# thermo_final.net
KiCad netlist of a schematic drawn in EAGLE
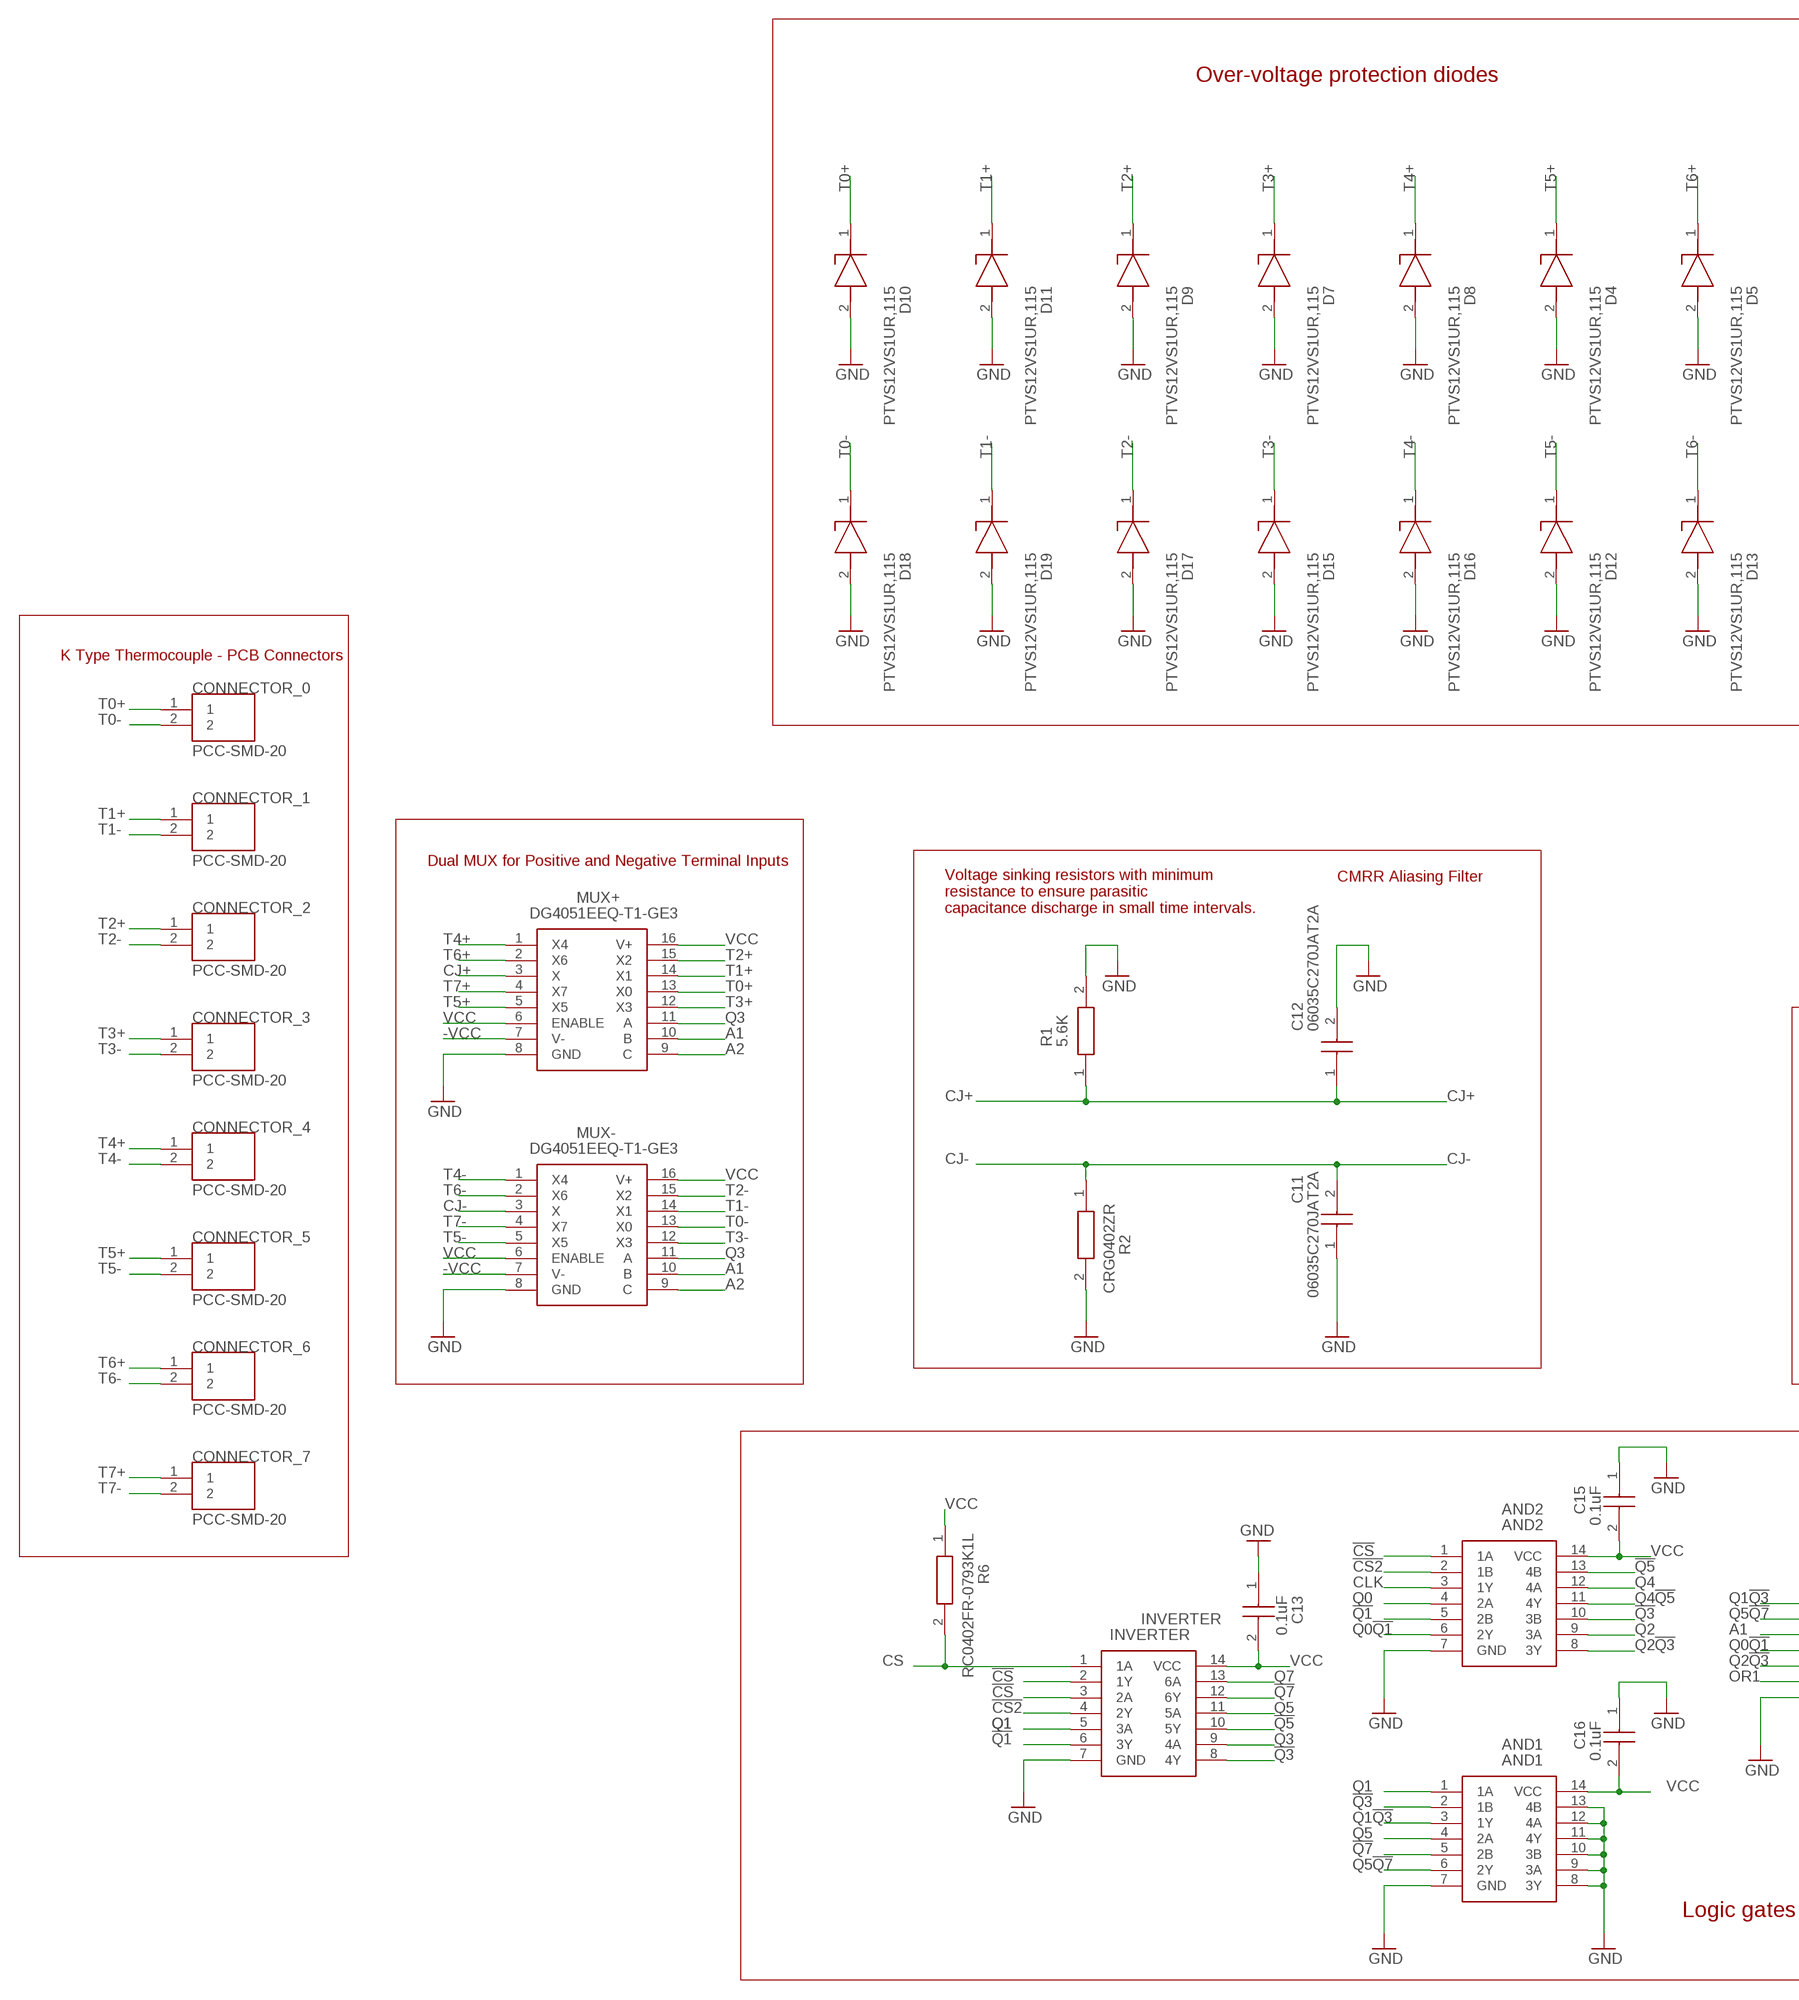
[diagram p0: schematic, sheet 1, part 1 of 2]
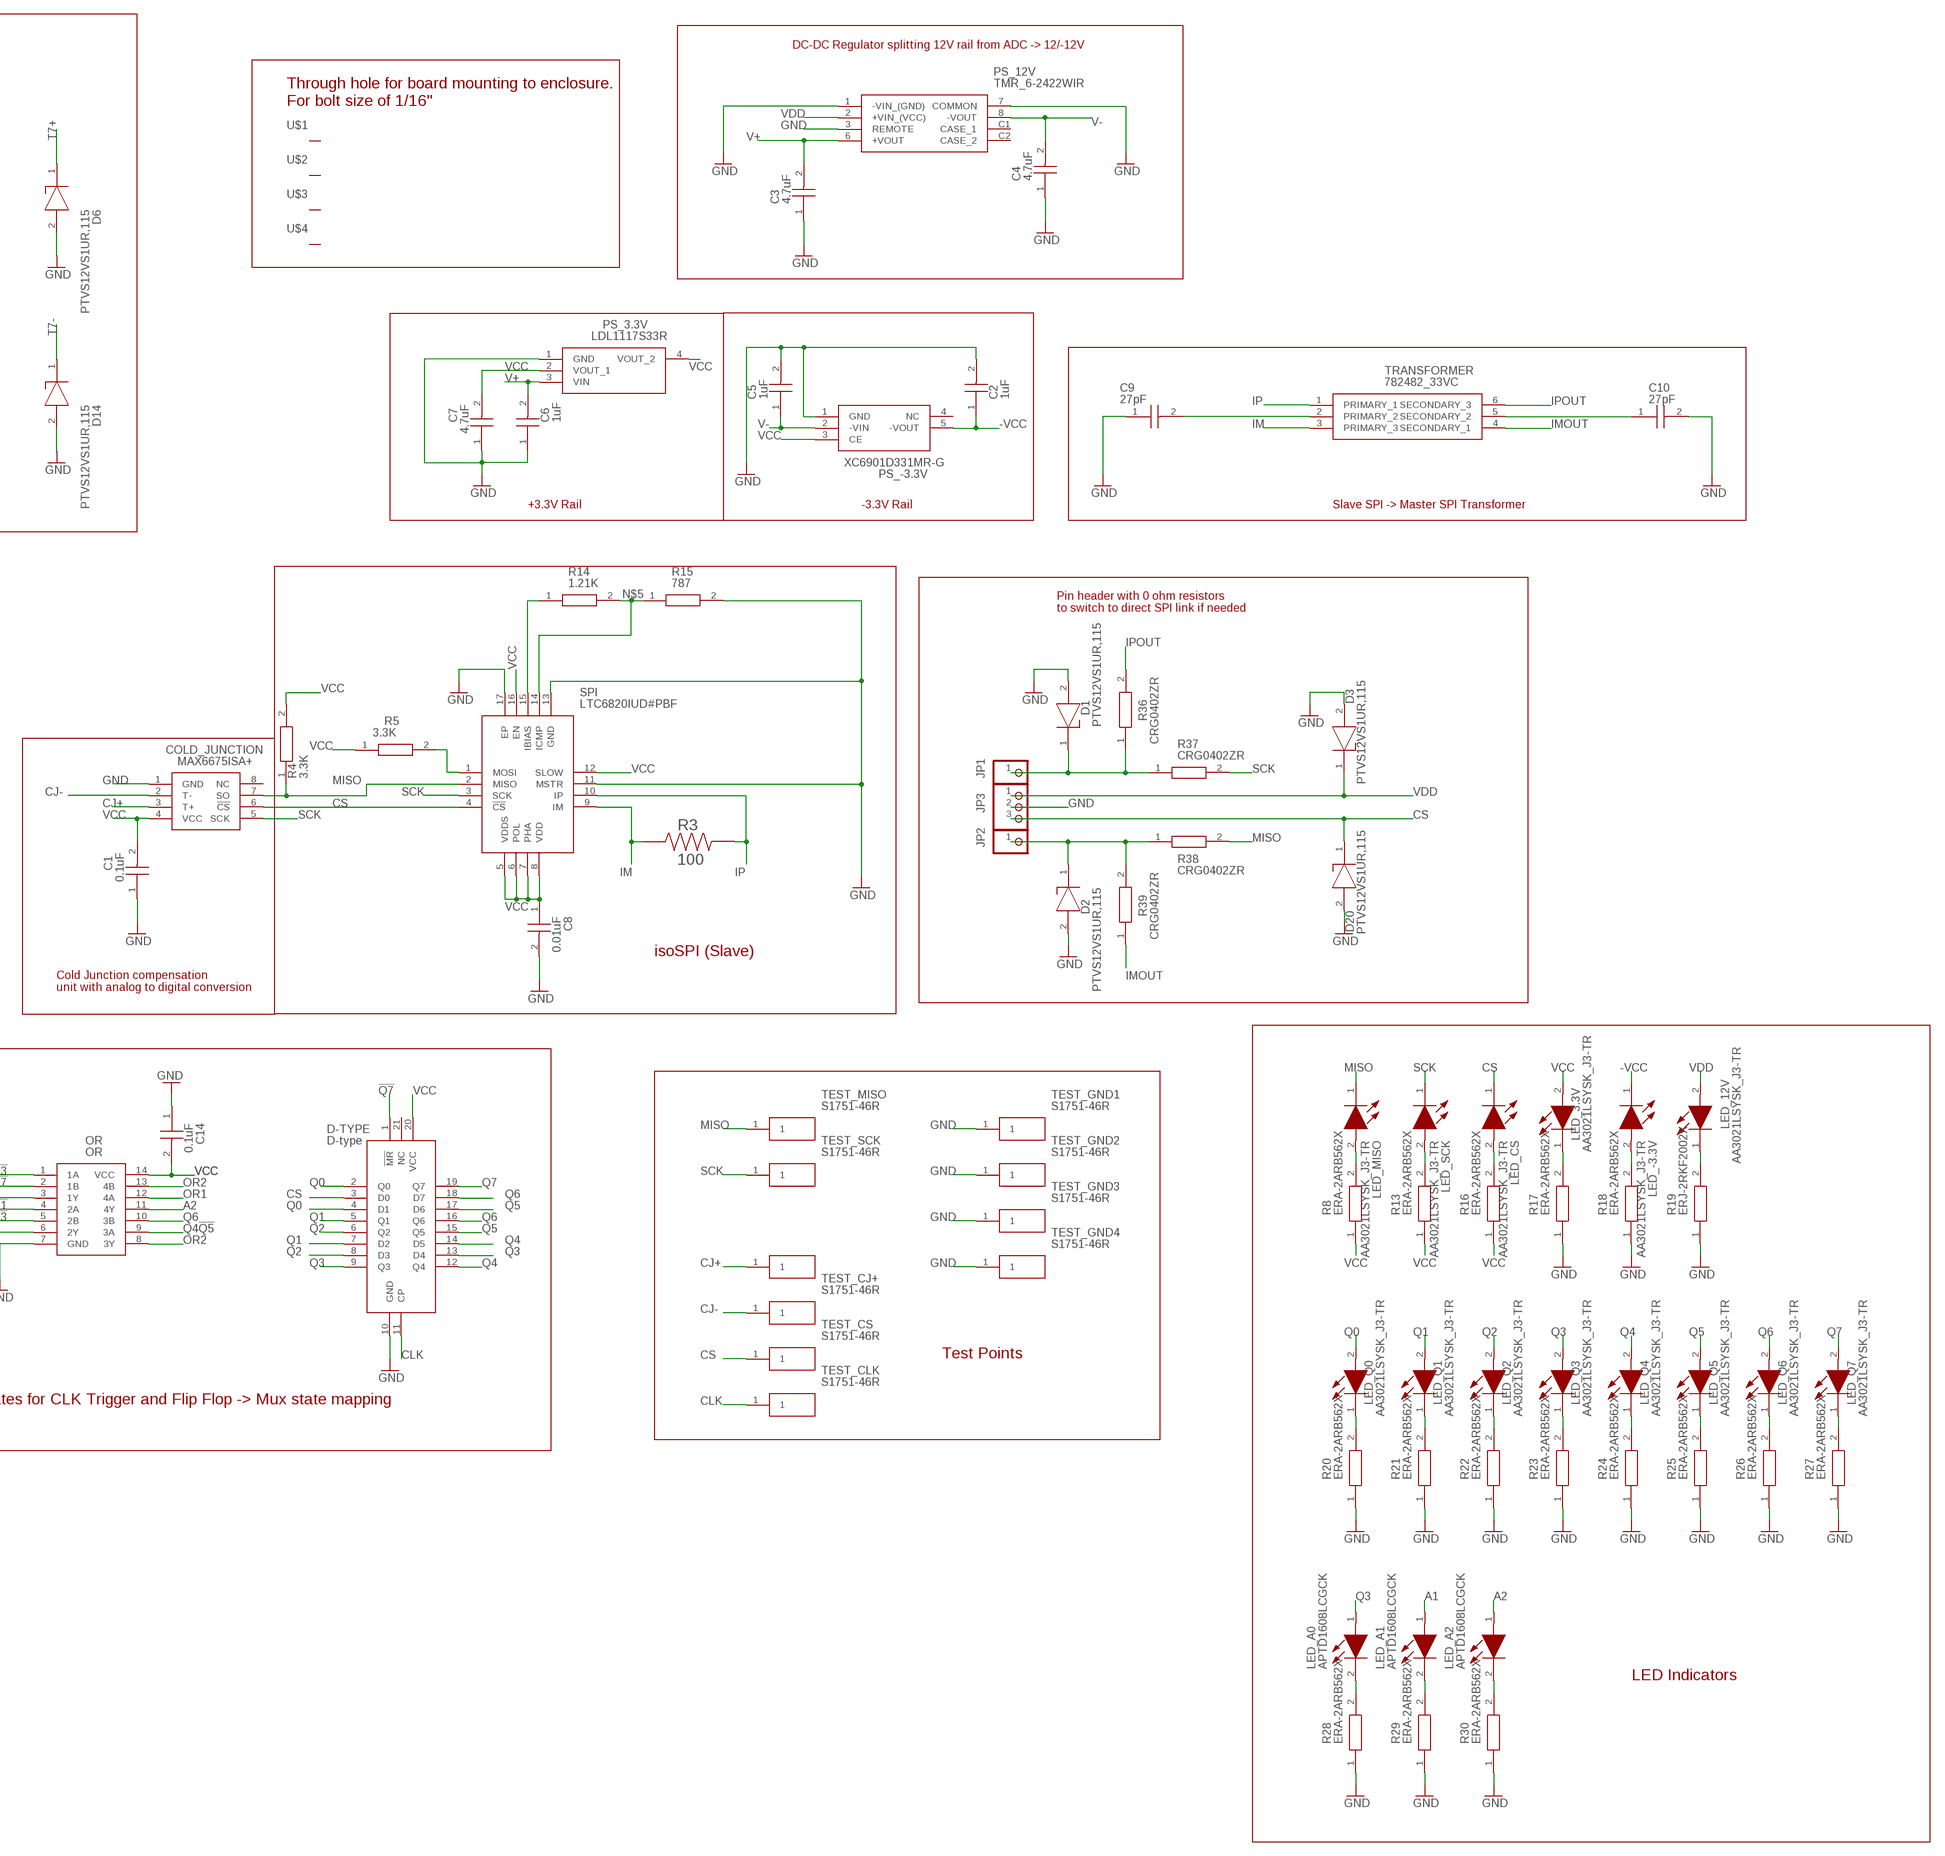
[diagram p1: schematic, sheet 1, part 2 of 2]

(export (version "E")
  (design (tool "Eeschema 10.0.6"))
  (components
    (comp (ref "AND1")
      (value "AND1")
      (footprint "eagle-import:SOIC127P600X175-14N")
      (fields
        (field (name "MANUFACTURER_PART_NUMBER") "SN74LVC08AMDREP")
        (field (name "MOUSER_PART_NUMBER") "595-SN74LVC08AMDREP")
      )
      (libsource (lib "eagle-import") (part "SN74LVC08AMDREP"))
    )
    (comp (ref "AND2")
      (value "AND2")
      (footprint "eagle-import:SOIC127P600X175-14N")
      (fields
        (field (name "MANUFACTURER_PART_NUMBER") "SN74LVC08AMDREP")
        (field (name "MOUSER_PART_NUMBER") "595-SN74LVC08AMDREP")
      )
      (libsource (lib "eagle-import") (part "SN74LVC08AMDREP"))
    )
    (comp (ref "C1")
      (value "0.1uF")
      (footprint "eagle-import:CAPC1608X90N")
      (fields
        (field (name "MANUFACTURER_PART_NUMBER") "CGA3E2X7R1H104K080AE")
        (field (name "MOUSER_PART_NUMBER") "810-CGA3E2X7R1H104KE")
      )
      (libsource (lib "eagle-import") (part "CGA3E2X7R1H104K080AE"))
    )
    (comp (ref "C2")
      (value "1uF")
      (footprint "eagle-import:CAPC1608X90N")
      (fields
        (field (name "MANUFACTURER_PART_NUMBER") "CGA3E1X7R1V105K080AC")
        (field (name "MOUSER_PART_NUMBER") "810-CGA3E1X7R1V105KC")
      )
      (libsource (lib "eagle-import") (part "CGA3E1X7R1V105K080AC"))
    )
    (comp (ref "C3")
      (value "4.7uF")
      (footprint "eagle-import:CAPC1608X90N")
      (fields
        (field (name "MANUFACTURER_PART_NUMBER") "JMK107BB7475KA-T")
        (field (name "MOUSER_PART_NUMBER") "963-JMK107BB7475KA-T")
      )
      (libsource (lib "eagle-import") (part "JMK107BB7475KA-T"))
    )
    (comp (ref "C4")
      (value "4.7uF")
      (footprint "eagle-import:CAPC1608X90N")
      (fields
        (field (name "MANUFACTURER_PART_NUMBER") "JMK107BB7475KA-T")
        (field (name "MOUSER_PART_NUMBER") "963-JMK107BB7475KA-T")
      )
      (libsource (lib "eagle-import") (part "JMK107BB7475KA-T"))
    )
    (comp (ref "C5")
      (value "1uF")
      (footprint "eagle-import:CAPC1608X90N")
      (fields
        (field (name "MANUFACTURER_PART_NUMBER") "CGA3E1X7R1V105K080AC")
        (field (name "MOUSER_PART_NUMBER") "810-CGA3E1X7R1V105KC")
      )
      (libsource (lib "eagle-import") (part "CGA3E1X7R1V105K080AC"))
    )
    (comp (ref "C6")
      (value "1uF")
      (footprint "eagle-import:CAPC1608X90N")
      (fields
        (field (name "MANUFACTURER_PART_NUMBER") "CGA3E1X7R1V105K080AC")
        (field (name "MOUSER_PART_NUMBER") "810-CGA3E1X7R1V105KC")
      )
      (libsource (lib "eagle-import") (part "CGA3E1X7R1V105K080AC"))
    )
    (comp (ref "C7")
      (value "4.7uF")
      (footprint "eagle-import:CAPC1608X90N")
      (fields
        (field (name "MANUFACTURER_PART_NUMBER") "JMK107BB7475KA-T")
        (field (name "MOUSER_PART_NUMBER") "963-JMK107BB7475KA-T")
      )
      (libsource (lib "eagle-import") (part "JMK107BB7475KA-T"))
    )
    (comp (ref "C8")
      (value "0.01uF")
      (footprint "eagle-import:CAPC1005X55N")
      (fields
        (field (name "MANUFACTURER_PART_NUMBER") "C0402C103J5RECAUTO")
        (field (name "MOUSER_PART_NUMBER") "80-C0402C103J5RECAUT")
      )
      (libsource (lib "eagle-import") (part "C0402C103J5RECAUTO"))
    )
    (comp (ref "C9")
      (value "27pF")
      (footprint "eagle-import:CAPC1608X90N")
      (fields (field (name "MANUFACTURER_PART_NUMBER") "06035C270JAT2A"))
      (libsource (lib "eagle-import") (part "06035C270JAT2A"))
    )
    (comp (ref "C10")
      (value "27pF")
      (footprint "eagle-import:CAPC1608X90N")
      (fields (field (name "MANUFACTURER_PART_NUMBER") "06035C270JAT2A"))
      (libsource (lib "eagle-import") (part "06035C270JAT2A"))
    )
    (comp (ref "C11")
      (value "06035C270JAT2A")
      (footprint "eagle-import:CAPC1608X90N")
      (libsource (lib "eagle-import") (part "06035C270JAT2A"))
    )
    (comp (ref "C12")
      (value "06035C270JAT2A")
      (footprint "eagle-import:CAPC1608X90N")
      (libsource (lib "eagle-import") (part "06035C270JAT2A"))
    )
    (comp (ref "C13")
      (value "0.1uF")
      (footprint "eagle-import:CAPC1608X90N")
      (fields
        (field (name "MANUFACTURER_PART_NUMBER") "CGA3E2X7R1H104K080AE")
        (field (name "MOUSER_PART_NUMBER") "810-CGA3E2X7R1H104KE")
      )
      (libsource (lib "eagle-import") (part "CGA3E2X7R1H104K080AE"))
    )
    (comp (ref "C14")
      (value "0.1uF")
      (footprint "eagle-import:CAPC1608X90N")
      (fields
        (field (name "MANUFACTURER_PART_NUMBER") "CGA3E2X7R1H104K080AE")
        (field (name "MOUSER_PART_NUMBER") "810-CGA3E2X7R1H104KE")
      )
      (libsource (lib "eagle-import") (part "CGA3E2X7R1H104K080AE"))
    )
    (comp (ref "C15")
      (value "0.1uF")
      (footprint "eagle-import:CAPC1608X90N")
      (fields
        (field (name "MANUFACTURER_PART_NUMBER") "CGA3E2X7R1H104K080AE")
        (field (name "MOUSER_PART_NUMBER") "810-CGA3E2X7R1H104KE")
      )
      (libsource (lib "eagle-import") (part "CGA3E2X7R1H104K080AE"))
    )
    (comp (ref "C16")
      (value "0.1uF")
      (footprint "eagle-import:CAPC1608X90N")
      (fields
        (field (name "MANUFACTURER_PART_NUMBER") "CGA3E2X7R1H104K080AE")
        (field (name "MOUSER_PART_NUMBER") "810-CGA3E2X7R1H104KE")
      )
      (libsource (lib "eagle-import") (part "CGA3E2X7R1H104K080AE"))
    )
    (comp (ref "COLD_JUNCTION")
      (value "MAX6675ISA+")
      (footprint "eagle-import:SOIC127P600X175-8N")
      (fields (field (name "MOUSER_PART_NUMBER") "700-MAX6675ISA"))
      (libsource (lib "eagle-import") (part "MAX6675ISA+"))
    )
    (comp (ref "CONNECTOR_0")
      (value "PCC-SMD-20")
      (footprint "eagle-import:OMEGA_PCC-SMD-20")
      (fields (field (name "MF") "Omega Engineering"))
      (libsource (lib "eagle-import") (part "PCC-SMD-20"))
    )
    (comp (ref "CONNECTOR_1")
      (value "PCC-SMD-20")
      (footprint "eagle-import:OMEGA_PCC-SMD-20")
      (fields (field (name "MF") "Omega Engineering"))
      (libsource (lib "eagle-import") (part "PCC-SMD-20"))
    )
    (comp (ref "CONNECTOR_2")
      (value "PCC-SMD-20")
      (footprint "eagle-import:OMEGA_PCC-SMD-20")
      (fields (field (name "MF") "Omega Engineering"))
      (libsource (lib "eagle-import") (part "PCC-SMD-20"))
    )
    (comp (ref "CONNECTOR_3")
      (value "PCC-SMD-20")
      (footprint "eagle-import:OMEGA_PCC-SMD-20")
      (fields (field (name "MF") "Omega Engineering"))
      (libsource (lib "eagle-import") (part "PCC-SMD-20"))
    )
    (comp (ref "CONNECTOR_4")
      (value "PCC-SMD-20")
      (footprint "eagle-import:OMEGA_PCC-SMD-20")
      (fields (field (name "MF") "Omega Engineering"))
      (libsource (lib "eagle-import") (part "PCC-SMD-20"))
    )
    (comp (ref "CONNECTOR_5")
      (value "PCC-SMD-20")
      (footprint "eagle-import:OMEGA_PCC-SMD-20")
      (fields (field (name "MF") "Omega Engineering"))
      (libsource (lib "eagle-import") (part "PCC-SMD-20"))
    )
    (comp (ref "CONNECTOR_6")
      (value "PCC-SMD-20")
      (footprint "eagle-import:OMEGA_PCC-SMD-20")
      (fields (field (name "MF") "Omega Engineering"))
      (libsource (lib "eagle-import") (part "PCC-SMD-20"))
    )
    (comp (ref "CONNECTOR_7")
      (value "PCC-SMD-20")
      (footprint "eagle-import:OMEGA_PCC-SMD-20")
      (fields (field (name "MF") "Omega Engineering"))
      (libsource (lib "eagle-import") (part "PCC-SMD-20"))
    )
    (comp (ref "D-TYPE")
      (value "D-type")
      (footprint "eagle-import:QFN50P450X250X100-21N")
      (fields
        (field (name "MANUFACTURER_PART_NUMBER") "74AHC273BQ,115")
        (field (name "MOUSER_PART_NUMBER") "771-AHC273BQ115")
      )
      (libsource (lib "eagle-import") (part "74AHC273BQ,115"))
    )
    (comp (ref "D1")
      (value "PTVS12VS1UR,115")
      (footprint "eagle-import:SOD123W")
      (fields (field (name "MOUSER_PART_NUMBER") "771-PTVS12VS1UR115"))
      (libsource (lib "eagle-import") (part "PTVS12VS1UR,115"))
    )
    (comp (ref "D2")
      (value "PTVS12VS1UR,115")
      (footprint "eagle-import:SOD123W")
      (fields (field (name "MOUSER_PART_NUMBER") "771-PTVS12VS1UR115"))
      (libsource (lib "eagle-import") (part "PTVS12VS1UR,115"))
    )
    (comp (ref "D3")
      (value "PTVS12VS1UR,115")
      (footprint "eagle-import:SOD123W")
      (fields (field (name "MOUSER_PART_NUMBER") "771-PTVS12VS1UR115"))
      (libsource (lib "eagle-import") (part "PTVS12VS1UR,115"))
    )
    (comp (ref "D4")
      (value "PTVS12VS1UR,115")
      (footprint "eagle-import:SOD123W")
      (fields (field (name "MOUSER_PART_NUMBER") "771-PTVS12VS1UR115"))
      (libsource (lib "eagle-import") (part "PTVS12VS1UR,115"))
    )
    (comp (ref "D5")
      (value "PTVS12VS1UR,115")
      (footprint "eagle-import:SOD123W")
      (fields (field (name "MOUSER_PART_NUMBER") "771-PTVS12VS1UR115"))
      (libsource (lib "eagle-import") (part "PTVS12VS1UR,115"))
    )
    (comp (ref "D6")
      (value "PTVS12VS1UR,115")
      (footprint "eagle-import:SOD123W")
      (fields (field (name "MOUSER_PART_NUMBER") "771-PTVS12VS1UR115"))
      (libsource (lib "eagle-import") (part "PTVS12VS1UR,115"))
    )
    (comp (ref "D7")
      (value "PTVS12VS1UR,115")
      (footprint "eagle-import:SOD123W")
      (fields (field (name "MOUSER_PART_NUMBER") "771-PTVS12VS1UR115"))
      (libsource (lib "eagle-import") (part "PTVS12VS1UR,115"))
    )
    (comp (ref "D8")
      (value "PTVS12VS1UR,115")
      (footprint "eagle-import:SOD123W")
      (fields (field (name "MOUSER_PART_NUMBER") "771-PTVS12VS1UR115"))
      (libsource (lib "eagle-import") (part "PTVS12VS1UR,115"))
    )
    (comp (ref "D9")
      (value "PTVS12VS1UR,115")
      (footprint "eagle-import:SOD123W")
      (fields (field (name "MOUSER_PART_NUMBER") "771-PTVS12VS1UR115"))
      (libsource (lib "eagle-import") (part "PTVS12VS1UR,115"))
    )
    (comp (ref "D10")
      (value "PTVS12VS1UR,115")
      (footprint "eagle-import:SOD123W")
      (fields (field (name "MOUSER_PART_NUMBER") "771-PTVS12VS1UR115"))
      (libsource (lib "eagle-import") (part "PTVS12VS1UR,115"))
    )
    (comp (ref "D11")
      (value "PTVS12VS1UR,115")
      (footprint "eagle-import:SOD123W")
      (fields (field (name "MOUSER_PART_NUMBER") "771-PTVS12VS1UR115"))
      (libsource (lib "eagle-import") (part "PTVS12VS1UR,115"))
    )
    (comp (ref "D12")
      (value "PTVS12VS1UR,115")
      (footprint "eagle-import:SOD123W")
      (fields (field (name "MOUSER_PART_NUMBER") "771-PTVS12VS1UR115"))
      (libsource (lib "eagle-import") (part "PTVS12VS1UR,115"))
    )
    (comp (ref "D13")
      (value "PTVS12VS1UR,115")
      (footprint "eagle-import:SOD123W")
      (fields (field (name "MOUSER_PART_NUMBER") "771-PTVS12VS1UR115"))
      (libsource (lib "eagle-import") (part "PTVS12VS1UR,115"))
    )
    (comp (ref "D14")
      (value "PTVS12VS1UR,115")
      (footprint "eagle-import:SOD123W")
      (fields (field (name "MOUSER_PART_NUMBER") "771-PTVS12VS1UR115"))
      (libsource (lib "eagle-import") (part "PTVS12VS1UR,115"))
    )
    (comp (ref "D15")
      (value "PTVS12VS1UR,115")
      (footprint "eagle-import:SOD123W")
      (fields (field (name "MOUSER_PART_NUMBER") "771-PTVS12VS1UR115"))
      (libsource (lib "eagle-import") (part "PTVS12VS1UR,115"))
    )
    (comp (ref "D16")
      (value "PTVS12VS1UR,115")
      (footprint "eagle-import:SOD123W")
      (fields (field (name "MOUSER_PART_NUMBER") "771-PTVS12VS1UR115"))
      (libsource (lib "eagle-import") (part "PTVS12VS1UR,115"))
    )
    (comp (ref "D17")
      (value "PTVS12VS1UR,115")
      (footprint "eagle-import:SOD123W")
      (fields (field (name "MOUSER_PART_NUMBER") "771-PTVS12VS1UR115"))
      (libsource (lib "eagle-import") (part "PTVS12VS1UR,115"))
    )
    (comp (ref "D18")
      (value "PTVS12VS1UR,115")
      (footprint "eagle-import:SOD123W")
      (fields (field (name "MOUSER_PART_NUMBER") "771-PTVS12VS1UR115"))
      (libsource (lib "eagle-import") (part "PTVS12VS1UR,115"))
    )
    (comp (ref "D19")
      (value "PTVS12VS1UR,115")
      (footprint "eagle-import:SOD123W")
      (fields (field (name "MOUSER_PART_NUMBER") "771-PTVS12VS1UR115"))
      (libsource (lib "eagle-import") (part "PTVS12VS1UR,115"))
    )
    (comp (ref "D20")
      (value "PTVS12VS1UR,115")
      (footprint "eagle-import:SOD123W")
      (fields (field (name "MOUSER_PART_NUMBER") "771-PTVS12VS1UR115"))
      (libsource (lib "eagle-import") (part "PTVS12VS1UR,115"))
    )
    (comp (ref "INVERTER")
      (value "INVERTER")
      (footprint "eagle-import:SOIC127P600X175-14N")
      (fields
        (field (name "MANUFACTURER_PART_NUMBER") "SN74HCS05QDRQ1")
        (field (name "MOUSER_PART_NUMBER") "595-SN74HCS05QDRQ1")
      )
      (libsource (lib "eagle-import") (part "SN74HCS05QDRQ1"))
    )
    (comp (ref "JP1")
      (value "PINHD-1X1")
      (footprint "eagle-import:1X01")
      (libsource (lib "eagle-import") (part "PINHD-1X1"))
    )
    (comp (ref "JP2")
      (value "PINHD-1X1")
      (footprint "eagle-import:1X01")
      (libsource (lib "eagle-import") (part "PINHD-1X1"))
    )
    (comp (ref "JP3")
      (value "PINHD-1X3")
      (footprint "eagle-import:1X03")
      (libsource (lib "eagle-import") (part "PINHD-1X3"))
    )
    (comp (ref "LED_-3.3V")
      (value "AA3021LSYSK_J3-TR")
      (footprint "eagle-import:AA3021LSYSKJ3TR")
      (fields
        (field (name "MANUFACTURER_PART_NUMBER") "AA3021LSYSK/J3-TR")
        (field (name "MOUSER_PART_NUMBER") "604-AA3021LSYSK/J3TR")
      )
      (libsource (lib "eagle-import") (part "AA3021LSYSK_J3-TR"))
    )
    (comp (ref "LED_3.3V")
      (value "AA3021LSYSK_J3-TR")
      (footprint "eagle-import:AA3021LSYSKJ3TR")
      (fields
        (field (name "MANUFACTURER_PART_NUMBER") "AA3021LSYSK/J3-TR")
        (field (name "MOUSER_PART_NUMBER") "604-AA3021LSYSK/J3TR")
      )
      (libsource (lib "eagle-import") (part "AA3021LSYSK_J3-TR"))
    )
    (comp (ref "LED_12V")
      (value "AA3021LSYSK_J3-TR")
      (footprint "eagle-import:AA3021LSYSKJ3TR")
      (fields
        (field (name "MANUFACTURER_PART_NUMBER") "AA3021LSYSK/J3-TR")
        (field (name "MOUSER_PART_NUMBER") "604-AA3021LSYSK/J3TR")
      )
      (libsource (lib "eagle-import") (part "AA3021LSYSK_J3-TR"))
    )
    (comp (ref "LED_A0")
      (value "APTD1608LCGCK")
      (footprint "eagle-import:APT1608CGCK")
      (fields (field (name "MOUSER_PART_NUMBER") "604-APTD1608LCGCK"))
      (libsource (lib "eagle-import") (part "APTD1608LCGCK"))
    )
    (comp (ref "LED_A1")
      (value "APTD1608LCGCK")
      (footprint "eagle-import:APT1608CGCK")
      (fields (field (name "MOUSER_PART_NUMBER") "604-APTD1608LCGCK"))
      (libsource (lib "eagle-import") (part "APTD1608LCGCK"))
    )
    (comp (ref "LED_A2")
      (value "APTD1608LCGCK")
      (footprint "eagle-import:APT1608CGCK")
      (fields (field (name "MOUSER_PART_NUMBER") "604-APTD1608LCGCK"))
      (libsource (lib "eagle-import") (part "APTD1608LCGCK"))
    )
    (comp (ref "LED_CS")
      (value "AA3021LSYSK_J3-TR")
      (footprint "eagle-import:AA3021LSYSKJ3TR")
      (fields
        (field (name "MANUFACTURER_PART_NUMBER") "AA3021LSYSK/J3-TR")
        (field (name "MOUSER_PART_NUMBER") "604-AA3021LSYSK/J3TR")
      )
      (libsource (lib "eagle-import") (part "AA3021LSYSK_J3-TR"))
    )
    (comp (ref "LED_MISO")
      (value "AA3021LSYSK_J3-TR")
      (footprint "eagle-import:AA3021LSYSKJ3TR")
      (fields
        (field (name "MANUFACTURER_PART_NUMBER") "AA3021LSYSK/J3-TR")
        (field (name "MOUSER_PART_NUMBER") "604-AA3021LSYSK/J3TR")
      )
      (libsource (lib "eagle-import") (part "AA3021LSYSK_J3-TR"))
    )
    (comp (ref "LED_Q0")
      (value "AA3021LSYSK_J3-TR")
      (footprint "eagle-import:AA3021LSYSKJ3TR")
      (fields
        (field (name "MANUFACTURER_PART_NUMBER") "AA3021LSYSK/J3-TR")
        (field (name "MOUSER_PART_NUMBER") "604-AA3021LSYSK/J3TR")
      )
      (libsource (lib "eagle-import") (part "AA3021LSYSK_J3-TR"))
    )
    (comp (ref "LED_Q1")
      (value "AA3021LSYSK_J3-TR")
      (footprint "eagle-import:AA3021LSYSKJ3TR")
      (fields
        (field (name "MANUFACTURER_PART_NUMBER") "AA3021LSYSK/J3-TR")
        (field (name "MOUSER_PART_NUMBER") "604-AA3021LSYSK/J3TR")
      )
      (libsource (lib "eagle-import") (part "AA3021LSYSK_J3-TR"))
    )
    (comp (ref "LED_Q2")
      (value "AA3021LSYSK_J3-TR")
      (footprint "eagle-import:AA3021LSYSKJ3TR")
      (fields
        (field (name "MANUFACTURER_PART_NUMBER") "AA3021LSYSK/J3-TR")
        (field (name "MOUSER_PART_NUMBER") "604-AA3021LSYSK/J3TR")
      )
      (libsource (lib "eagle-import") (part "AA3021LSYSK_J3-TR"))
    )
    (comp (ref "LED_Q3")
      (value "AA3021LSYSK_J3-TR")
      (footprint "eagle-import:AA3021LSYSKJ3TR")
      (fields
        (field (name "MANUFACTURER_PART_NUMBER") "AA3021LSYSK/J3-TR")
        (field (name "MOUSER_PART_NUMBER") "604-AA3021LSYSK/J3TR")
      )
      (libsource (lib "eagle-import") (part "AA3021LSYSK_J3-TR"))
    )
    (comp (ref "LED_Q4")
      (value "AA3021LSYSK_J3-TR")
      (footprint "eagle-import:AA3021LSYSKJ3TR")
      (fields
        (field (name "MANUFACTURER_PART_NUMBER") "AA3021LSYSK/J3-TR")
        (field (name "MOUSER_PART_NUMBER") "604-AA3021LSYSK/J3TR")
      )
      (libsource (lib "eagle-import") (part "AA3021LSYSK_J3-TR"))
    )
    (comp (ref "LED_Q5")
      (value "AA3021LSYSK_J3-TR")
      (footprint "eagle-import:AA3021LSYSKJ3TR")
      (fields
        (field (name "MANUFACTURER_PART_NUMBER") "AA3021LSYSK/J3-TR")
        (field (name "MOUSER_PART_NUMBER") "604-AA3021LSYSK/J3TR")
      )
      (libsource (lib "eagle-import") (part "AA3021LSYSK_J3-TR"))
    )
    (comp (ref "LED_Q6")
      (value "AA3021LSYSK_J3-TR")
      (footprint "eagle-import:AA3021LSYSKJ3TR")
      (fields
        (field (name "MANUFACTURER_PART_NUMBER") "AA3021LSYSK/J3-TR")
        (field (name "MOUSER_PART_NUMBER") "604-AA3021LSYSK/J3TR")
      )
      (libsource (lib "eagle-import") (part "AA3021LSYSK_J3-TR"))
    )
    (comp (ref "LED_Q7")
      (value "AA3021LSYSK_J3-TR")
      (footprint "eagle-import:AA3021LSYSKJ3TR")
      (fields
        (field (name "MANUFACTURER_PART_NUMBER") "AA3021LSYSK/J3-TR")
        (field (name "MOUSER_PART_NUMBER") "604-AA3021LSYSK/J3TR")
      )
      (libsource (lib "eagle-import") (part "AA3021LSYSK_J3-TR"))
    )
    (comp (ref "LED_SCK")
      (value "AA3021LSYSK_J3-TR")
      (footprint "eagle-import:AA3021LSYSKJ3TR")
      (fields
        (field (name "MANUFACTURER_PART_NUMBER") "AA3021LSYSK/J3-TR")
        (field (name "MOUSER_PART_NUMBER") "604-AA3021LSYSK/J3TR")
      )
      (libsource (lib "eagle-import") (part "AA3021LSYSK_J3-TR"))
    )
    (comp (ref "MUX+")
      (value "DG4051EEQ-T1-GE3")
      (footprint "eagle-import:SOP65P640X120-16N")
      (fields (field (name "MOUSER_PART_NUMBER") "78-DG4051EEQ-T1-GE3"))
      (libsource (lib "eagle-import") (part "DG4051EEQ-T1-GE3"))
    )
    (comp (ref "MUX-")
      (value "DG4051EEQ-T1-GE3")
      (footprint "eagle-import:SOP65P640X120-16N")
      (fields (field (name "MOUSER_PART_NUMBER") "78-DG4051EEQ-T1-GE3"))
      (libsource (lib "eagle-import") (part "DG4051EEQ-T1-GE3"))
    )
    (comp (ref "OR")
      (value "OR")
      (footprint "eagle-import:SOIC127P600X175-14N")
      (fields
        (field (name "MANUFACTURER_PART_NUMBER") "SN74LV32ADE4")
        (field (name "MOUSER_PART_NUMBER") "595-SN74LV32ADE4")
      )
      (libsource (lib "eagle-import") (part "SN74LV32ADE4"))
    )
    (comp (ref "PS_-3.3V")
      (value "XC6901D331MR-G")
      (footprint "eagle-import:SOT95P280X130-5N")
      (fields (field (name "MOUSER_PART_NUMBER") "865-XC6901D331MR-G"))
      (libsource (lib "eagle-import") (part "XC6901D331MR-G"))
    )
    (comp (ref "PS_3.3V")
      (value "LDL1117S33R")
      (footprint "eagle-import:SOT230P700X180-4N")
      (fields (field (name "MOUSER_PART_NUMBER") "511-LDL1117S33R"))
      (libsource (lib "eagle-import") (part "LDL1117S33R"))
    )
    (comp (ref "PS_12V")
      (value "TMR_6-2422WIR")
      (footprint "eagle-import:TMR67212WIR")
      (fields
        (field (name "MANUFACTURER_PART_NUMBER") "TMR 6-2422WIR")
        (field (name "MOUSER_PART_NUMBER") "495-TMR6-2422WIR")
      )
      (libsource (lib "eagle-import") (part "TMR_6-2422WIR"))
    )
    (comp (ref "R1")
      (value "5.6K")
      (footprint "eagle-import:ERA2AED122X")
      (fields
        (field (name "MANUFACTURER_PART_NUMBER") "ERA-2ARB562X")
        (field (name "MOUSER_PART_NUMBER") "667-ERA-2ARB562X")
      )
      (libsource (lib "eagle-import") (part "ERA-2ARB562X"))
    )
    (comp (ref "R2")
      (value "CRG0402ZR")
      (footprint "eagle-import:RESC1005X40N")
      (fields (field (name "MOUSER_PART_NUMBER") "279-CRG0402ZR"))
      (libsource (lib "eagle-import") (part "CRG0402ZR"))
    )
    (comp (ref "R3")
      (value "100")
      (footprint "eagle-import:RESC1005X40N")
      (fields (field (name "MF") "Vishay") (field (name "MP") "TNPW0402100RBYEP"))
      (libsource (lib "eagle-import") (part "TNPW0402100RBYEP"))
    )
    (comp (ref "R4")
      (value "3.3K")
      (footprint "eagle-import:RESC1005X40N")
      (fields
        (field (name "MANUFACTURER_PART_NUMBER") "RC0402JR-133K3L")
        (field (name "MOUSER_PART_NUMBER") "603-RC0402JR-133K3L")
      )
      (libsource (lib "eagle-import") (part "RC0402JR-133K3L"))
    )
    (comp (ref "R5")
      (value "3.3K")
      (footprint "eagle-import:RESC1005X40N")
      (fields
        (field (name "MANUFACTURER_PART_NUMBER") "RC0402JR-133K3L")
        (field (name "MOUSER_PART_NUMBER") "603-RC0402JR-133K3L")
      )
      (libsource (lib "eagle-import") (part "RC0402JR-133K3L"))
    )
    (comp (ref "R6")
      (value "RC0402FR-0793K1L")
      (footprint "eagle-import:RESC1005X40N")
      (fields (field (name "MOUSER_PART_NUMBER") "603-RC0402FR-0793K1L"))
      (libsource (lib "eagle-import") (part "RC0402FR-0793K1L"))
    )
    (comp (ref "R8")
      (value "ERA-2ARB562X")
      (footprint "eagle-import:ERA2AED122X")
      (fields (field (name "MOUSER_PART_NUMBER") "667-ERA-2ARB562X"))
      (libsource (lib "eagle-import") (part "ERA-2ARB562X"))
    )
    (comp (ref "R13")
      (value "ERA-2ARB562X")
      (footprint "eagle-import:ERA2AED122X")
      (fields (field (name "MOUSER_PART_NUMBER") "667-ERA-2ARB562X"))
      (libsource (lib "eagle-import") (part "ERA-2ARB562X"))
    )
    (comp (ref "R14")
      (value "1.21K")
      (footprint "eagle-import:RESC1005X35N")
      (fields (field (name "MANUFACTURER_PART_NUMBER") "CPF0402B1K21E1"))
      (libsource (lib "eagle-import") (part "CPF0402B1K21E1"))
    )
    (comp (ref "R15")
      (value "787")
      (footprint "eagle-import:ERA2AED122X")
      (fields (field (name "MANUFACTURER_PART_NUMBER") "ERA-2AEB7870X"))
      (libsource (lib "eagle-import") (part "ERA-2AEB7870X"))
    )
    (comp (ref "R16")
      (value "ERA-2ARB562X")
      (footprint "eagle-import:ERA2AED122X")
      (fields (field (name "MOUSER_PART_NUMBER") "667-ERA-2ARB562X"))
      (libsource (lib "eagle-import") (part "ERA-2ARB562X"))
    )
    (comp (ref "R17")
      (value "ERA-2ARB562X")
      (footprint "eagle-import:ERA2AED122X")
      (fields (field (name "MOUSER_PART_NUMBER") "667-ERA-2ARB562X"))
      (libsource (lib "eagle-import") (part "ERA-2ARB562X"))
    )
    (comp (ref "R18")
      (value "ERA-2ARB562X")
      (footprint "eagle-import:ERA2AED122X")
      (fields (field (name "MOUSER_PART_NUMBER") "667-ERA-2ARB562X"))
      (libsource (lib "eagle-import") (part "ERA-2ARB562X"))
    )
    (comp (ref "R19")
      (value "ERJ-2RKF2002X")
      (footprint "eagle-import:ERJ2R_(0402)")
      (fields (field (name "MOUSER_PART_NUMBER") "667-ERJ-2RKF2002X"))
      (libsource (lib "eagle-import") (part "ERJ-2RKF2002X"))
    )
    (comp (ref "R20")
      (value "ERA-2ARB562X")
      (footprint "eagle-import:ERA2AED122X")
      (fields (field (name "MOUSER_PART_NUMBER") "667-ERA-2ARB562X"))
      (libsource (lib "eagle-import") (part "ERA-2ARB562X"))
    )
    (comp (ref "R21")
      (value "ERA-2ARB562X")
      (footprint "eagle-import:ERA2AED122X")
      (fields (field (name "MOUSER_PART_NUMBER") "667-ERA-2ARB562X"))
      (libsource (lib "eagle-import") (part "ERA-2ARB562X"))
    )
    (comp (ref "R22")
      (value "ERA-2ARB562X")
      (footprint "eagle-import:ERA2AED122X")
      (fields (field (name "MOUSER_PART_NUMBER") "667-ERA-2ARB562X"))
      (libsource (lib "eagle-import") (part "ERA-2ARB562X"))
    )
    (comp (ref "R23")
      (value "ERA-2ARB562X")
      (footprint "eagle-import:ERA2AED122X")
      (fields (field (name "MOUSER_PART_NUMBER") "667-ERA-2ARB562X"))
      (libsource (lib "eagle-import") (part "ERA-2ARB562X"))
    )
    (comp (ref "R24")
      (value "ERA-2ARB562X")
      (footprint "eagle-import:ERA2AED122X")
      (fields (field (name "MOUSER_PART_NUMBER") "667-ERA-2ARB562X"))
      (libsource (lib "eagle-import") (part "ERA-2ARB562X"))
    )
    (comp (ref "R25")
      (value "ERA-2ARB562X")
      (footprint "eagle-import:ERA2AED122X")
      (fields (field (name "MOUSER_PART_NUMBER") "667-ERA-2ARB562X"))
      (libsource (lib "eagle-import") (part "ERA-2ARB562X"))
    )
    (comp (ref "R26")
      (value "ERA-2ARB562X")
      (footprint "eagle-import:ERA2AED122X")
      (fields (field (name "MOUSER_PART_NUMBER") "667-ERA-2ARB562X"))
      (libsource (lib "eagle-import") (part "ERA-2ARB562X"))
    )
    (comp (ref "R27")
      (value "ERA-2ARB562X")
      (footprint "eagle-import:ERA2AED122X")
      (fields (field (name "MOUSER_PART_NUMBER") "667-ERA-2ARB562X"))
      (libsource (lib "eagle-import") (part "ERA-2ARB562X"))
    )
    (comp (ref "R28")
      (value "ERA-2ARB562X")
      (footprint "eagle-import:ERA2AED122X")
      (fields (field (name "MOUSER_PART_NUMBER") "667-ERA-2ARB562X"))
      (libsource (lib "eagle-import") (part "ERA-2ARB562X"))
    )
    (comp (ref "R29")
      (value "ERA-2ARB562X")
      (footprint "eagle-import:ERA2AED122X")
      (fields (field (name "MOUSER_PART_NUMBER") "667-ERA-2ARB562X"))
      (libsource (lib "eagle-import") (part "ERA-2ARB562X"))
    )
    (comp (ref "R30")
      (value "ERA-2ARB562X")
      (footprint "eagle-import:ERA2AED122X")
      (fields (field (name "MOUSER_PART_NUMBER") "667-ERA-2ARB562X"))
      (libsource (lib "eagle-import") (part "ERA-2ARB562X"))
    )
    (comp (ref "R36")
      (value "CRG0402ZR")
      (footprint "eagle-import:RESC1005X40N")
      (fields (field (name "MOUSER_PART_NUMBER") "279-CRG0402ZR"))
      (libsource (lib "eagle-import") (part "CRG0402ZR"))
    )
    (comp (ref "R37")
      (value "CRG0402ZR")
      (footprint "eagle-import:RESC1005X40N")
      (fields (field (name "MOUSER_PART_NUMBER") "279-CRG0402ZR"))
      (libsource (lib "eagle-import") (part "CRG0402ZR"))
    )
    (comp (ref "R38")
      (value "CRG0402ZR")
      (footprint "eagle-import:RESC1005X40N")
      (fields (field (name "MOUSER_PART_NUMBER") "279-CRG0402ZR"))
      (libsource (lib "eagle-import") (part "CRG0402ZR"))
    )
    (comp (ref "R39")
      (value "CRG0402ZR")
      (footprint "eagle-import:RESC1005X40N")
      (fields (field (name "MOUSER_PART_NUMBER") "279-CRG0402ZR"))
      (libsource (lib "eagle-import") (part "CRG0402ZR"))
    )
    (comp (ref "SPI")
      (value "LTC6820IUD#PBF")
      (footprint "eagle-import:QFN50P300X300X80-17N")
      (fields (field (name "MOUSER_PART_NUMBER") "584-LTC6820IUD#PBF"))
      (libsource (lib "eagle-import") (part "LTC6820IUD#PBF"))
    )
    (comp (ref "TEST_CJ+")
      (value "S1751-46R")
      (footprint "eagle-import:S175146R")
      (fields (field (name "MOUSER_PART_NUMBER") "855-S1751-46R"))
      (libsource (lib "eagle-import") (part "S1751-46R"))
    )
    (comp (ref "TEST_CJ-")
      (value "S1751-46R")
      (footprint "eagle-import:S175146R")
      (fields (field (name "MOUSER_PART_NUMBER") "855-S1751-46R"))
      (libsource (lib "eagle-import") (part "S1751-46R"))
    )
    (comp (ref "TEST_CLK")
      (value "S1751-46R")
      (footprint "eagle-import:S175146R")
      (fields (field (name "MOUSER_PART_NUMBER") "855-S1751-46R"))
      (libsource (lib "eagle-import") (part "S1751-46R"))
    )
    (comp (ref "TEST_CS")
      (value "S1751-46R")
      (footprint "eagle-import:S175146R")
      (fields (field (name "MOUSER_PART_NUMBER") "855-S1751-46R"))
      (libsource (lib "eagle-import") (part "S1751-46R"))
    )
    (comp (ref "TEST_GND1")
      (value "S1751-46R")
      (footprint "eagle-import:S175146R")
      (fields (field (name "MOUSER_PART_NUMBER") "855-S1751-46R"))
      (libsource (lib "eagle-import") (part "S1751-46R"))
    )
    (comp (ref "TEST_GND2")
      (value "S1751-46R")
      (footprint "eagle-import:S175146R")
      (fields (field (name "MOUSER_PART_NUMBER") "855-S1751-46R"))
      (libsource (lib "eagle-import") (part "S1751-46R"))
    )
    (comp (ref "TEST_GND3")
      (value "S1751-46R")
      (footprint "eagle-import:S175146R")
      (fields (field (name "MOUSER_PART_NUMBER") "855-S1751-46R"))
      (libsource (lib "eagle-import") (part "S1751-46R"))
    )
    (comp (ref "TEST_GND4")
      (value "S1751-46R")
      (footprint "eagle-import:S175146R")
      (fields (field (name "MOUSER_PART_NUMBER") "855-S1751-46R"))
      (libsource (lib "eagle-import") (part "S1751-46R"))
    )
    (comp (ref "TEST_MISO")
      (value "S1751-46R")
      (footprint "eagle-import:S175146R")
      (fields (field (name "MOUSER_PART_NUMBER") "855-S1751-46R"))
      (libsource (lib "eagle-import") (part "S1751-46R"))
    )
    (comp (ref "TEST_SCK")
      (value "S1751-46R")
      (footprint "eagle-import:S175146R")
      (fields (field (name "MOUSER_PART_NUMBER") "855-S1751-46R"))
      (libsource (lib "eagle-import") (part "S1751-46R"))
    )
    (comp (ref "TRANSFORMER")
      (value "782482_33VC")
      (footprint "eagle-import:DIP1016W60P254L914H635Q6N")
      (fields
        (field (name "MANUFACTURER_PART_NUMBER") "782482/33VC")
        (field (name "MOUSER_PART_NUMBER") "580-782482/33VC")
      )
      (libsource (lib "eagle-import") (part "782482_33VC"))
    )
    (comp (ref "U$1")
      (value "THROUGH_HOLE")
      (footprint "eagle-import:THROUGH_HOLE")
      (libsource (lib "eagle-import") (part "THROUGH_HOLE"))
    )
    (comp (ref "U$2")
      (value "THROUGH_HOLE")
      (footprint "eagle-import:THROUGH_HOLE")
      (libsource (lib "eagle-import") (part "THROUGH_HOLE"))
    )
    (comp (ref "U$3")
      (value "THROUGH_HOLE")
      (footprint "eagle-import:THROUGH_HOLE")
      (libsource (lib "eagle-import") (part "THROUGH_HOLE"))
    )
    (comp (ref "U$4")
      (value "THROUGH_HOLE")
      (footprint "eagle-import:THROUGH_HOLE")
      (libsource (lib "eagle-import") (part "THROUGH_HOLE"))
    )
  )
  (nets
    (net (code "1") (name "/-VCC") (class "Default")
      (node (ref "C2") (pin "1") (pinfunction "1_1") (pintype "bidirectional"))
      (node (ref "LED_-3.3V") (pin "1") (pinfunction "K_1") (pintype "bidirectional"))
      (node (ref "MUX+") (pin "7") (pinfunction "V-_7") (pintype "bidirectional"))
      (node (ref "MUX-") (pin "7") (pinfunction "V-_7") (pintype "bidirectional"))
      (node (ref "PS_-3.3V") (pin "5") (pinfunction "-VOUT_5") (pintype "output"))
    )
    (net (code "2") (name "/A1") (class "Default")
      (node (ref "LED_A1") (pin "1") (pinfunction "A_1") (pintype "bidirectional"))
      (node (ref "MUX+") (pin "10") (pinfunction "B_10") (pintype "bidirectional"))
      (node (ref "MUX-") (pin "10") (pinfunction "B_10") (pintype "bidirectional"))
      (node (ref "OR") (pin "3") (pinfunction "1Y_3") (pintype "bidirectional"))
    )
    (net (code "3") (name "/A2") (class "Default")
      (node (ref "LED_A2") (pin "1") (pinfunction "A_1") (pintype "bidirectional"))
      (node (ref "MUX+") (pin "9") (pinfunction "C_9") (pintype "bidirectional"))
      (node (ref "MUX-") (pin "9") (pinfunction "C_9") (pintype "bidirectional"))
      (node (ref "OR") (pin "11") (pinfunction "4Y_11") (pintype "bidirectional"))
    )
    (net (code "4") (name "/CJ+") (class "Default")
      (node (ref "C12") (pin "1") (pinfunction "1_1") (pintype "bidirectional"))
      (node (ref "COLD_JUNCTION") (pin "3") (pinfunction "T+_3") (pintype "bidirectional"))
      (node (ref "MUX+") (pin "3") (pinfunction "X_3") (pintype "bidirectional"))
      (node (ref "R1") (pin "1") (pinfunction "1_1") (pintype "bidirectional"))
      (node (ref "TEST_CJ-") (pin "1") (pinfunction "1_1") (pintype "bidirectional"))
    )
    (net (code "5") (name "/CJ-") (class "Default")
      (node (ref "C11") (pin "2") (pinfunction "2_2") (pintype "bidirectional"))
      (node (ref "COLD_JUNCTION") (pin "2") (pinfunction "T-_2") (pintype "bidirectional"))
      (node (ref "MUX-") (pin "3") (pinfunction "X_3") (pintype "bidirectional"))
      (node (ref "R2") (pin "1") (pinfunction "1_1") (pintype "bidirectional"))
      (node (ref "TEST_CJ+") (pin "1") (pinfunction "1_1") (pintype "bidirectional"))
    )
    (net (code "6") (name "/CLK") (class "Default")
      (node (ref "AND2") (pin "3") (pinfunction "1Y_3") (pintype "bidirectional"))
      (node (ref "D-TYPE") (pin "11") (pinfunction "CP_11") (pintype "bidirectional"))
      (node (ref "TEST_CLK") (pin "1") (pinfunction "1_1") (pintype "bidirectional"))
    )
    (net (code "7") (name "/CS") (class "Default")
      (node (ref "COLD_JUNCTION") (pin "6") (pinfunction "~{CS}_6") (pintype "bidirectional"))
      (node (ref "D-TYPE") (pin "3") (pinfunction "D0_3") (pintype "bidirectional"))
      (node (ref "D20") (pin "1") (pinfunction "K_1") (pintype "bidirectional"))
      (node (ref "INVERTER") (pin "1") (pinfunction "1A_1") (pintype "bidirectional"))
      (node (ref "JP3") (pin "3") (pinfunction "3_3") (pintype "passive"))
      (node (ref "LED_CS") (pin "1") (pinfunction "K_1") (pintype "bidirectional"))
      (node (ref "R6") (pin "2") (pinfunction "2_2") (pintype "bidirectional"))
      (node (ref "SPI") (pin "4") (pinfunction "~{CS}_4") (pintype "bidirectional"))
      (node (ref "TEST_CS") (pin "1") (pinfunction "1_1") (pintype "bidirectional"))
    )
    (net (code "8") (name "/IM") (class "Default")
      (node (ref "R3") (pin "1") (pinfunction "1_1") (pintype "passive"))
      (node (ref "SPI") (pin "9") (pinfunction "IM_9") (pintype "bidirectional"))
      (node (ref "TRANSFORMER") (pin "3") (pinfunction "PRIMARY_3_3") (pintype "bidirectional"))
    )
    (net (code "9") (name "/IMOUT") (class "Default")
      (node (ref "R39") (pin "1") (pinfunction "1_1") (pintype "bidirectional"))
      (node (ref "TRANSFORMER") (pin "4") (pinfunction "SECONDARY_1_4") (pintype "bidirectional"))
    )
    (net (code "10") (name "/IP") (class "Default")
      (node (ref "R3") (pin "2") (pinfunction "2_2") (pintype "passive"))
      (node (ref "SPI") (pin "10") (pinfunction "IP_10") (pintype "bidirectional"))
      (node (ref "TRANSFORMER") (pin "1") (pinfunction "PRIMARY_1_1") (pintype "bidirectional"))
    )
    (net (code "11") (name "/IPOUT") (class "Default")
      (node (ref "R36") (pin "2") (pinfunction "2_2") (pintype "bidirectional"))
      (node (ref "TRANSFORMER") (pin "6") (pinfunction "SECONDARY_3_6") (pintype "bidirectional"))
    )
    (net (code "12") (name "/MISO") (class "Default")
      (node (ref "COLD_JUNCTION") (pin "7") (pinfunction "SO_7") (pintype "bidirectional"))
      (node (ref "LED_MISO") (pin "1") (pinfunction "K_1") (pintype "bidirectional"))
      (node (ref "R38") (pin "2") (pinfunction "2_2") (pintype "bidirectional"))
      (node (ref "R4") (pin "1") (pinfunction "1_1") (pintype "bidirectional"))
      (node (ref "SPI") (pin "2") (pinfunction "MISO_2") (pintype "bidirectional"))
      (node (ref "TEST_MISO") (pin "1") (pinfunction "1_1") (pintype "bidirectional"))
    )
    (net (code "13") (name "/N$5") (class "Default")
      (node (ref "R14") (pin "2") (pinfunction "2_2") (pintype "bidirectional"))
      (node (ref "R15") (pin "1") (pinfunction "1_1") (pintype "bidirectional"))
      (node (ref "SPI") (pin "14") (pinfunction "ICMP_14") (pintype "bidirectional"))
    )
    (net (code "14") (name "/OR1") (class "Default")
      (node (ref "OR") (pin "12") (pinfunction "4A_12") (pintype "bidirectional"))
      (node (ref "OR") (pin "6") (pinfunction "2Y_6") (pintype "bidirectional"))
    )
    (net (code "15") (name "/OR2") (class "Default")
      (node (ref "OR") (pin "13") (pinfunction "4B_13") (pintype "bidirectional"))
      (node (ref "OR") (pin "8") (pinfunction "3Y_8") (pintype "bidirectional"))
    )
    (net (code "16") (name "/Q0") (class "Default")
      (node (ref "AND2") (pin "4") (pinfunction "2A_4") (pintype "bidirectional"))
      (node (ref "D-TYPE") (pin "2") (pinfunction "Q0_2") (pintype "bidirectional"))
      (node (ref "D-TYPE") (pin "4") (pinfunction "D1_4") (pintype "bidirectional"))
      (node (ref "LED_Q0") (pin "2") (pinfunction "A_2") (pintype "bidirectional"))
    )
    (net (code "17") (name "/Q0~{Q1}") (class "Default")
      (node (ref "AND2") (pin "6") (pinfunction "2Y_6") (pintype "bidirectional"))
      (node (ref "OR") (pin "4") (pinfunction "2A_4") (pintype "bidirectional"))
    )
    (net (code "18") (name "/Q1") (class "Default")
      (node (ref "AND1") (pin "1") (pinfunction "1A_1") (pintype "bidirectional"))
      (node (ref "D-TYPE") (pin "5") (pinfunction "Q1_5") (pintype "bidirectional"))
      (node (ref "D-TYPE") (pin "7") (pinfunction "D2_7") (pintype "bidirectional"))
      (node (ref "INVERTER") (pin "5") (pinfunction "3A_5") (pintype "bidirectional"))
      (node (ref "LED_Q1") (pin "2") (pinfunction "A_2") (pintype "bidirectional"))
    )
    (net (code "19") (name "/Q1~{Q3}") (class "Default")
      (node (ref "AND1") (pin "3") (pinfunction "1Y_3") (pintype "bidirectional"))
      (node (ref "OR") (pin "1") (pinfunction "1A_1") (pintype "bidirectional"))
    )
    (net (code "20") (name "/Q2") (class "Default")
      (node (ref "AND2") (pin "9") (pinfunction "3A_9") (pintype "bidirectional"))
      (node (ref "D-TYPE") (pin "6") (pinfunction "Q2_6") (pintype "bidirectional"))
      (node (ref "D-TYPE") (pin "8") (pinfunction "D3_8") (pintype "bidirectional"))
      (node (ref "LED_Q2") (pin "2") (pinfunction "A_2") (pintype "bidirectional"))
    )
    (net (code "21") (name "/Q2~{Q3}") (class "Default")
      (node (ref "AND2") (pin "8") (pinfunction "3Y_8") (pintype "bidirectional"))
      (node (ref "OR") (pin "5") (pinfunction "2B_5") (pintype "bidirectional"))
    )
    (net (code "22") (name "/Q3") (class "Default")
      (node (ref "D-TYPE") (pin "13") (pinfunction "D4_13") (pintype "bidirectional"))
      (node (ref "D-TYPE") (pin "9") (pinfunction "Q3_9") (pintype "bidirectional"))
      (node (ref "INVERTER") (pin "9") (pinfunction "4A_9") (pintype "bidirectional"))
      (node (ref "LED_A0") (pin "1") (pinfunction "A_1") (pintype "bidirectional"))
      (node (ref "LED_Q3") (pin "2") (pinfunction "A_2") (pintype "bidirectional"))
      (node (ref "MUX+") (pin "11") (pinfunction "A_11") (pintype "bidirectional"))
      (node (ref "MUX-") (pin "11") (pinfunction "A_11") (pintype "bidirectional"))
    )
    (net (code "23") (name "/Q4") (class "Default")
      (node (ref "AND2") (pin "12") (pinfunction "4A_12") (pintype "bidirectional"))
      (node (ref "D-TYPE") (pin "12") (pinfunction "Q4_12") (pintype "bidirectional"))
      (node (ref "D-TYPE") (pin "14") (pinfunction "D5_14") (pintype "bidirectional"))
      (node (ref "LED_Q4") (pin "2") (pinfunction "A_2") (pintype "bidirectional"))
    )
    (net (code "24") (name "/Q4~{Q5}") (class "Default")
      (node (ref "AND2") (pin "11") (pinfunction "4Y_11") (pintype "bidirectional"))
      (node (ref "OR") (pin "9") (pinfunction "3A_9") (pintype "bidirectional"))
    )
    (net (code "25") (name "/Q5") (class "Default")
      (node (ref "AND1") (pin "4") (pinfunction "2A_4") (pintype "bidirectional"))
      (node (ref "D-TYPE") (pin "15") (pinfunction "Q5_15") (pintype "bidirectional"))
      (node (ref "D-TYPE") (pin "17") (pinfunction "D6_17") (pintype "bidirectional"))
      (node (ref "INVERTER") (pin "11") (pinfunction "5A_11") (pintype "bidirectional"))
      (node (ref "LED_Q5") (pin "2") (pinfunction "A_2") (pintype "bidirectional"))
    )
    (net (code "26") (name "/Q5~{Q7}") (class "Default")
      (node (ref "AND1") (pin "6") (pinfunction "2Y_6") (pintype "bidirectional"))
      (node (ref "OR") (pin "2") (pinfunction "1B_2") (pintype "bidirectional"))
    )
    (net (code "27") (name "/Q6") (class "Default")
      (node (ref "D-TYPE") (pin "16") (pinfunction "Q6_16") (pintype "bidirectional"))
      (node (ref "D-TYPE") (pin "18") (pinfunction "D7_18") (pintype "bidirectional"))
      (node (ref "LED_Q6") (pin "2") (pinfunction "A_2") (pintype "bidirectional"))
      (node (ref "OR") (pin "10") (pinfunction "3B_10") (pintype "bidirectional"))
    )
    (net (code "28") (name "/Q7") (class "Default")
      (node (ref "D-TYPE") (pin "19") (pinfunction "Q7_19") (pintype "bidirectional"))
      (node (ref "INVERTER") (pin "13") (pinfunction "6A_13") (pintype "bidirectional"))
      (node (ref "LED_Q7") (pin "2") (pinfunction "A_2") (pintype "bidirectional"))
    )
    (net (code "29") (name "/SCK") (class "Default")
      (node (ref "COLD_JUNCTION") (pin "5") (pinfunction "SCK_5") (pintype "bidirectional"))
      (node (ref "LED_SCK") (pin "1") (pinfunction "K_1") (pintype "bidirectional"))
      (node (ref "R37") (pin "2") (pinfunction "2_2") (pintype "bidirectional"))
      (node (ref "SPI") (pin "3") (pinfunction "SCK_3") (pintype "bidirectional"))
      (node (ref "TEST_SCK") (pin "1") (pinfunction "1_1") (pintype "bidirectional"))
    )
    (net (code "30") (name "/T0+") (class "Default")
      (node (ref "CONNECTOR_0") (pin "1") (pinfunction "1_1") (pintype "passive"))
      (node (ref "D10") (pin "1") (pinfunction "K_1") (pintype "bidirectional"))
      (node (ref "MUX+") (pin "13") (pinfunction "X0_13") (pintype "bidirectional"))
    )
    (net (code "31") (name "/T0-") (class "Default")
      (node (ref "CONNECTOR_0") (pin "2") (pinfunction "2_2") (pintype "passive"))
      (node (ref "D18") (pin "1") (pinfunction "K_1") (pintype "bidirectional"))
      (node (ref "MUX-") (pin "13") (pinfunction "X0_13") (pintype "bidirectional"))
    )
    (net (code "32") (name "/T1+") (class "Default")
      (node (ref "CONNECTOR_1") (pin "1") (pinfunction "1_1") (pintype "passive"))
      (node (ref "D11") (pin "1") (pinfunction "K_1") (pintype "bidirectional"))
      (node (ref "MUX+") (pin "14") (pinfunction "X1_14") (pintype "bidirectional"))
    )
    (net (code "33") (name "/T1-") (class "Default")
      (node (ref "CONNECTOR_1") (pin "2") (pinfunction "2_2") (pintype "passive"))
      (node (ref "D19") (pin "1") (pinfunction "K_1") (pintype "bidirectional"))
      (node (ref "MUX-") (pin "14") (pinfunction "X1_14") (pintype "bidirectional"))
    )
    (net (code "34") (name "/T2+") (class "Default")
      (node (ref "CONNECTOR_2") (pin "1") (pinfunction "1_1") (pintype "passive"))
      (node (ref "D9") (pin "1") (pinfunction "K_1") (pintype "bidirectional"))
      (node (ref "MUX+") (pin "15") (pinfunction "X2_15") (pintype "bidirectional"))
    )
    (net (code "35") (name "/T2-") (class "Default")
      (node (ref "CONNECTOR_2") (pin "2") (pinfunction "2_2") (pintype "passive"))
      (node (ref "D17") (pin "1") (pinfunction "K_1") (pintype "bidirectional"))
      (node (ref "MUX-") (pin "15") (pinfunction "X2_15") (pintype "bidirectional"))
    )
    (net (code "36") (name "/T3+") (class "Default")
      (node (ref "CONNECTOR_3") (pin "1") (pinfunction "1_1") (pintype "passive"))
      (node (ref "D7") (pin "1") (pinfunction "K_1") (pintype "bidirectional"))
      (node (ref "MUX+") (pin "12") (pinfunction "X3_12") (pintype "bidirectional"))
    )
    (net (code "37") (name "/T3-") (class "Default")
      (node (ref "CONNECTOR_3") (pin "2") (pinfunction "2_2") (pintype "passive"))
      (node (ref "D15") (pin "1") (pinfunction "K_1") (pintype "bidirectional"))
      (node (ref "MUX-") (pin "12") (pinfunction "X3_12") (pintype "bidirectional"))
    )
    (net (code "38") (name "/T4+") (class "Default")
      (node (ref "CONNECTOR_4") (pin "1") (pinfunction "1_1") (pintype "passive"))
      (node (ref "D8") (pin "1") (pinfunction "K_1") (pintype "bidirectional"))
      (node (ref "MUX+") (pin "1") (pinfunction "X4_1") (pintype "bidirectional"))
    )
    (net (code "39") (name "/T4-") (class "Default")
      (node (ref "CONNECTOR_4") (pin "2") (pinfunction "2_2") (pintype "passive"))
      (node (ref "D16") (pin "1") (pinfunction "K_1") (pintype "bidirectional"))
      (node (ref "MUX-") (pin "1") (pinfunction "X4_1") (pintype "bidirectional"))
    )
    (net (code "40") (name "/T5+") (class "Default")
      (node (ref "CONNECTOR_5") (pin "1") (pinfunction "1_1") (pintype "passive"))
      (node (ref "D4") (pin "1") (pinfunction "K_1") (pintype "bidirectional"))
      (node (ref "MUX+") (pin "5") (pinfunction "X5_5") (pintype "bidirectional"))
    )
    (net (code "41") (name "/T5-") (class "Default")
      (node (ref "CONNECTOR_5") (pin "2") (pinfunction "2_2") (pintype "passive"))
      (node (ref "D12") (pin "1") (pinfunction "K_1") (pintype "bidirectional"))
      (node (ref "MUX-") (pin "5") (pinfunction "X5_5") (pintype "bidirectional"))
    )
    (net (code "42") (name "/T6+") (class "Default")
      (node (ref "CONNECTOR_6") (pin "1") (pinfunction "1_1") (pintype "passive"))
      (node (ref "D5") (pin "1") (pinfunction "K_1") (pintype "bidirectional"))
      (node (ref "MUX+") (pin "2") (pinfunction "X6_2") (pintype "bidirectional"))
    )
    (net (code "43") (name "/T6-") (class "Default")
      (node (ref "CONNECTOR_6") (pin "2") (pinfunction "2_2") (pintype "passive"))
      (node (ref "D13") (pin "1") (pinfunction "K_1") (pintype "bidirectional"))
      (node (ref "MUX-") (pin "2") (pinfunction "X6_2") (pintype "bidirectional"))
    )
    (net (code "44") (name "/T7+") (class "Default")
      (node (ref "CONNECTOR_7") (pin "1") (pinfunction "1_1") (pintype "passive"))
      (node (ref "D6") (pin "1") (pinfunction "K_1") (pintype "bidirectional"))
      (node (ref "MUX+") (pin "4") (pinfunction "X7_4") (pintype "bidirectional"))
    )
    (net (code "45") (name "/T7-") (class "Default")
      (node (ref "CONNECTOR_7") (pin "2") (pinfunction "2_2") (pintype "passive"))
      (node (ref "D14") (pin "1") (pinfunction "K_1") (pintype "bidirectional"))
      (node (ref "MUX-") (pin "4") (pinfunction "X7_4") (pintype "bidirectional"))
    )
    (net (code "46") (name "/V+") (class "Default")
      (node (ref "C3") (pin "2") (pinfunction "2_2") (pintype "bidirectional"))
      (node (ref "C6") (pin "2") (pinfunction "2_2") (pintype "bidirectional"))
      (node (ref "PS_12V") (pin "6") (pinfunction "+VOUT_6") (pintype "bidirectional"))
      (node (ref "PS_3.3V") (pin "3") (pinfunction "VIN_3") (pintype "input"))
    )
    (net (code "47") (name "/V-") (class "Default")
      (node (ref "C4") (pin "2") (pinfunction "2_2") (pintype "bidirectional"))
      (node (ref "C5") (pin "1") (pinfunction "1_1") (pintype "bidirectional"))
      (node (ref "PS_-3.3V") (pin "2") (pinfunction "-VIN_2") (pintype "input"))
      (node (ref "PS_12V") (pin "8") (pinfunction "-VOUT_8") (pintype "bidirectional"))
    )
    (net (code "48") (name "/VCC") (class "Default")
      (node (ref "AND1") (pin "14") (pinfunction "VCC_14") (pintype "bidirectional"))
      (node (ref "AND2") (pin "14") (pinfunction "VCC_14") (pintype "bidirectional"))
      (node (ref "C1") (pin "2") (pinfunction "2_2") (pintype "bidirectional"))
      (node (ref "C13") (pin "2") (pinfunction "2_2") (pintype "bidirectional"))
      (node (ref "C14") (pin "2") (pinfunction "2_2") (pintype "bidirectional"))
      (node (ref "C15") (pin "2") (pinfunction "2_2") (pintype "bidirectional"))
      (node (ref "C16") (pin "2") (pinfunction "2_2") (pintype "bidirectional"))
      (node (ref "C7") (pin "2") (pinfunction "2_2") (pintype "bidirectional"))
      (node (ref "C8") (pin "1") (pinfunction "1_1") (pintype "bidirectional"))
      (node (ref "COLD_JUNCTION") (pin "4") (pinfunction "VCC_4") (pintype "bidirectional"))
      (node (ref "D-TYPE") (pin "20") (pinfunction "VCC_20") (pintype "bidirectional"))
      (node (ref "INVERTER") (pin "14") (pinfunction "VCC_14") (pintype "bidirectional"))
      (node (ref "LED_3.3V") (pin "2") (pinfunction "A_2") (pintype "bidirectional"))
      (node (ref "MUX+") (pin "16") (pinfunction "V+_16") (pintype "bidirectional"))
      (node (ref "MUX+") (pin "6") (pinfunction "ENABLE_6") (pintype "bidirectional"))
      (node (ref "MUX-") (pin "16") (pinfunction "V+_16") (pintype "bidirectional"))
      (node (ref "MUX-") (pin "6") (pinfunction "ENABLE_6") (pintype "bidirectional"))
      (node (ref "OR") (pin "14") (pinfunction "VCC_14") (pintype "bidirectional"))
      (node (ref "PS_-3.3V") (pin "3") (pinfunction "CE_3") (pintype "input"))
      (node (ref "PS_3.3V") (pin "2") (pinfunction "VOUT_1_2") (pintype "output"))
      (node (ref "PS_3.3V") (pin "4") (pinfunction "VOUT_2_4") (pintype "output"))
      (node (ref "R13") (pin "1") (pinfunction "1_1") (pintype "bidirectional"))
      (node (ref "R16") (pin "1") (pinfunction "1_1") (pintype "bidirectional"))
      (node (ref "R4") (pin "2") (pinfunction "2_2") (pintype "bidirectional"))
      (node (ref "R5") (pin "1") (pinfunction "1_1") (pintype "bidirectional"))
      (node (ref "R6") (pin "1") (pinfunction "1_1") (pintype "bidirectional"))
      (node (ref "R8") (pin "1") (pinfunction "1_1") (pintype "bidirectional"))
      (node (ref "SPI") (pin "12") (pinfunction "SLOW_12") (pintype "bidirectional"))
      (node (ref "SPI") (pin "16") (pinfunction "EN_16") (pintype "bidirectional"))
      (node (ref "SPI") (pin "5") (pinfunction "VDDS_5") (pintype "bidirectional"))
      (node (ref "SPI") (pin "6") (pinfunction "POL_6") (pintype "bidirectional"))
      (node (ref "SPI") (pin "7") (pinfunction "PHA_7") (pintype "bidirectional"))
      (node (ref "SPI") (pin "8") (pinfunction "VDD_8") (pintype "bidirectional"))
    )
    (net (code "49") (name "/VDD") (class "Default")
      (node (ref "D3") (pin "1") (pinfunction "K_1") (pintype "bidirectional"))
      (node (ref "JP3") (pin "1") (pinfunction "1_1") (pintype "passive"))
      (node (ref "LED_12V") (pin "2") (pinfunction "A_2") (pintype "bidirectional"))
      (node (ref "PS_12V") (pin "2") (pinfunction "+VIN_(VCC)_2") (pintype "bidirectional"))
    )
    (net (code "50") (name "/~{CS2}") (class "Default")
      (node (ref "AND2") (pin "2") (pinfunction "1B_2") (pintype "bidirectional"))
      (node (ref "INVERTER") (pin "4") (pinfunction "2Y_4") (pintype "bidirectional"))
    )
    (net (code "51") (name "/~{CS}") (class "Default")
      (node (ref "AND2") (pin "1") (pinfunction "1A_1") (pintype "bidirectional"))
      (node (ref "INVERTER") (pin "2") (pinfunction "1Y_2") (pintype "bidirectional"))
      (node (ref "INVERTER") (pin "3") (pinfunction "2A_3") (pintype "bidirectional"))
    )
    (net (code "52") (name "/~{Q1}") (class "Default")
      (node (ref "AND2") (pin "5") (pinfunction "2B_5") (pintype "bidirectional"))
      (node (ref "INVERTER") (pin "6") (pinfunction "3Y_6") (pintype "bidirectional"))
    )
    (net (code "53") (name "/~{Q3}") (class "Default")
      (node (ref "AND1") (pin "2") (pinfunction "1B_2") (pintype "bidirectional"))
      (node (ref "AND2") (pin "10") (pinfunction "3B_10") (pintype "bidirectional"))
      (node (ref "INVERTER") (pin "8") (pinfunction "4Y_8") (pintype "bidirectional"))
    )
    (net (code "54") (name "/~{Q5}") (class "Default")
      (node (ref "AND2") (pin "13") (pinfunction "4B_13") (pintype "bidirectional"))
      (node (ref "INVERTER") (pin "10") (pinfunction "5Y_10") (pintype "bidirectional"))
    )
    (net (code "55") (name "/~{Q7}") (class "Default")
      (node (ref "AND1") (pin "5") (pinfunction "2B_5") (pintype "bidirectional"))
      (node (ref "D-TYPE") (pin "1") (pinfunction "~{MR}_1") (pintype "bidirectional"))
      (node (ref "INVERTER") (pin "12") (pinfunction "6Y_12") (pintype "bidirectional"))
    )
    (net (code "56") (name "GND") (class "Default")
      (node (ref "AND1") (pin "10") (pinfunction "3B_10") (pintype "bidirectional"))
      (node (ref "AND1") (pin "11") (pinfunction "4Y_11") (pintype "bidirectional"))
      (node (ref "AND1") (pin "12") (pinfunction "4A_12") (pintype "bidirectional"))
      (node (ref "AND1") (pin "13") (pinfunction "4B_13") (pintype "bidirectional"))
      (node (ref "AND1") (pin "7") (pinfunction "GND_7") (pintype "bidirectional"))
      (node (ref "AND1") (pin "8") (pinfunction "3Y_8") (pintype "bidirectional"))
      (node (ref "AND1") (pin "9") (pinfunction "3A_9") (pintype "bidirectional"))
      (node (ref "AND2") (pin "7") (pinfunction "GND_7") (pintype "bidirectional"))
      (node (ref "C1") (pin "1") (pinfunction "1_1") (pintype "bidirectional"))
      (node (ref "C10") (pin "2") (pinfunction "2_2") (pintype "bidirectional"))
      (node (ref "C11") (pin "1") (pinfunction "1_1") (pintype "bidirectional"))
      (node (ref "C12") (pin "2") (pinfunction "2_2") (pintype "bidirectional"))
      (node (ref "C13") (pin "1") (pinfunction "1_1") (pintype "bidirectional"))
      (node (ref "C14") (pin "1") (pinfunction "1_1") (pintype "bidirectional"))
      (node (ref "C15") (pin "1") (pinfunction "1_1") (pintype "bidirectional"))
      (node (ref "C16") (pin "1") (pinfunction "1_1") (pintype "bidirectional"))
      (node (ref "C2") (pin "2") (pinfunction "2_2") (pintype "bidirectional"))
      (node (ref "C3") (pin "1") (pinfunction "1_1") (pintype "bidirectional"))
      (node (ref "C4") (pin "1") (pinfunction "1_1") (pintype "bidirectional"))
      (node (ref "C5") (pin "2") (pinfunction "2_2") (pintype "bidirectional"))
      (node (ref "C6") (pin "1") (pinfunction "1_1") (pintype "bidirectional"))
      (node (ref "C7") (pin "1") (pinfunction "1_1") (pintype "bidirectional"))
      (node (ref "C8") (pin "2") (pinfunction "2_2") (pintype "bidirectional"))
      (node (ref "C9") (pin "1") (pinfunction "1_1") (pintype "bidirectional"))
      (node (ref "COLD_JUNCTION") (pin "1") (pinfunction "GND_1") (pintype "bidirectional"))
      (node (ref "D-TYPE") (pin "10") (pinfunction "GND_10") (pintype "bidirectional"))
      (node (ref "D1") (pin "2") (pinfunction "A_2") (pintype "bidirectional"))
      (node (ref "D10") (pin "2") (pinfunction "A_2") (pintype "bidirectional"))
      (node (ref "D11") (pin "2") (pinfunction "A_2") (pintype "bidirectional"))
      (node (ref "D12") (pin "2") (pinfunction "A_2") (pintype "bidirectional"))
      (node (ref "D13") (pin "2") (pinfunction "A_2") (pintype "bidirectional"))
      (node (ref "D14") (pin "2") (pinfunction "A_2") (pintype "bidirectional"))
      (node (ref "D15") (pin "2") (pinfunction "A_2") (pintype "bidirectional"))
      (node (ref "D16") (pin "2") (pinfunction "A_2") (pintype "bidirectional"))
      (node (ref "D17") (pin "2") (pinfunction "A_2") (pintype "bidirectional"))
      (node (ref "D18") (pin "2") (pinfunction "A_2") (pintype "bidirectional"))
      (node (ref "D19") (pin "2") (pinfunction "A_2") (pintype "bidirectional"))
      (node (ref "D2") (pin "2") (pinfunction "A_2") (pintype "bidirectional"))
      (node (ref "D20") (pin "2") (pinfunction "A_2") (pintype "bidirectional"))
      (node (ref "D3") (pin "2") (pinfunction "A_2") (pintype "bidirectional"))
      (node (ref "D4") (pin "2") (pinfunction "A_2") (pintype "bidirectional"))
      (node (ref "D5") (pin "2") (pinfunction "A_2") (pintype "bidirectional"))
      (node (ref "D6") (pin "2") (pinfunction "A_2") (pintype "bidirectional"))
      (node (ref "D7") (pin "2") (pinfunction "A_2") (pintype "bidirectional"))
      (node (ref "D8") (pin "2") (pinfunction "A_2") (pintype "bidirectional"))
      (node (ref "D9") (pin "2") (pinfunction "A_2") (pintype "bidirectional"))
      (node (ref "INVERTER") (pin "7") (pinfunction "GND_7") (pintype "bidirectional"))
      (node (ref "JP3") (pin "2") (pinfunction "2_2") (pintype "passive"))
      (node (ref "MUX+") (pin "8") (pinfunction "GND_8") (pintype "bidirectional"))
      (node (ref "MUX-") (pin "8") (pinfunction "GND_8") (pintype "bidirectional"))
      (node (ref "OR") (pin "7") (pinfunction "GND_7") (pintype "bidirectional"))
      (node (ref "PS_-3.3V") (pin "1") (pinfunction "GND_1") (pintype "power_in"))
      (node (ref "PS_12V") (pin "1") (pinfunction "-VIN_(GND)_1") (pintype "bidirectional"))
      (node (ref "PS_12V") (pin "3") (pinfunction "REMOTE_3") (pintype "bidirectional"))
      (node (ref "PS_12V") (pin "7") (pinfunction "COMMON_7") (pintype "bidirectional"))
      (node (ref "PS_3.3V") (pin "1") (pinfunction "GND_1") (pintype "power_in"))
      (node (ref "R1") (pin "2") (pinfunction "2_2") (pintype "bidirectional"))
      (node (ref "R15") (pin "2") (pinfunction "2_2") (pintype "bidirectional"))
      (node (ref "R17") (pin "1") (pinfunction "1_1") (pintype "bidirectional"))
      (node (ref "R18") (pin "1") (pinfunction "1_1") (pintype "bidirectional"))
      (node (ref "R19") (pin "1") (pinfunction "1_1") (pintype "bidirectional"))
      (node (ref "R2") (pin "2") (pinfunction "2_2") (pintype "bidirectional"))
      (node (ref "R20") (pin "1") (pinfunction "1_1") (pintype "bidirectional"))
      (node (ref "R21") (pin "1") (pinfunction "1_1") (pintype "bidirectional"))
      (node (ref "R22") (pin "1") (pinfunction "1_1") (pintype "bidirectional"))
      (node (ref "R23") (pin "1") (pinfunction "1_1") (pintype "bidirectional"))
      (node (ref "R24") (pin "1") (pinfunction "1_1") (pintype "bidirectional"))
      (node (ref "R25") (pin "1") (pinfunction "1_1") (pintype "bidirectional"))
      (node (ref "R26") (pin "1") (pinfunction "1_1") (pintype "bidirectional"))
      (node (ref "R27") (pin "1") (pinfunction "1_1") (pintype "bidirectional"))
      (node (ref "R28") (pin "1") (pinfunction "1_1") (pintype "bidirectional"))
      (node (ref "R29") (pin "1") (pinfunction "1_1") (pintype "bidirectional"))
      (node (ref "R30") (pin "1") (pinfunction "1_1") (pintype "bidirectional"))
      (node (ref "SPI") (pin "11") (pinfunction "MSTR_11") (pintype "bidirectional"))
      (node (ref "SPI") (pin "13") (pinfunction "GND_13") (pintype "bidirectional"))
      (node (ref "SPI") (pin "17") (pinfunction "EP_17") (pintype "bidirectional"))
      (node (ref "TEST_GND1") (pin "1") (pinfunction "1_1") (pintype "bidirectional"))
      (node (ref "TEST_GND2") (pin "1") (pinfunction "1_1") (pintype "bidirectional"))
      (node (ref "TEST_GND3") (pin "1") (pinfunction "1_1") (pintype "bidirectional"))
      (node (ref "TEST_GND4") (pin "1") (pinfunction "1_1") (pintype "bidirectional"))
    )
    (net (code "57") (name "Net-(D1-K)") (class "Default")
      (node (ref "D1") (pin "1") (pinfunction "K_1") (pintype "bidirectional"))
      (node (ref "JP1") (pin "1") (pinfunction "1_1") (pintype "passive"))
      (node (ref "R36") (pin "1") (pinfunction "1_1") (pintype "bidirectional"))
      (node (ref "R37") (pin "1") (pinfunction "1_1") (pintype "bidirectional"))
    )
    (net (code "58") (name "Net-(D2-K)") (class "Default")
      (node (ref "D2") (pin "1") (pinfunction "K_1") (pintype "bidirectional"))
      (node (ref "JP2") (pin "1") (pinfunction "1_1") (pintype "passive"))
      (node (ref "R38") (pin "1") (pinfunction "1_1") (pintype "bidirectional"))
      (node (ref "R39") (pin "2") (pinfunction "2_2") (pintype "bidirectional"))
    )
    (net (code "59") (name "Net-(LED_-3.3V-A)") (class "Default")
      (node (ref "LED_-3.3V") (pin "2") (pinfunction "A_2") (pintype "bidirectional"))
      (node (ref "R18") (pin "2") (pinfunction "2_2") (pintype "bidirectional"))
    )
    (net (code "60") (name "Net-(LED_3.3V-K)") (class "Default")
      (node (ref "LED_3.3V") (pin "1") (pinfunction "K_1") (pintype "bidirectional"))
      (node (ref "R17") (pin "2") (pinfunction "2_2") (pintype "bidirectional"))
    )
    (net (code "61") (name "Net-(LED_12V-K)") (class "Default")
      (node (ref "LED_12V") (pin "1") (pinfunction "K_1") (pintype "bidirectional"))
      (node (ref "R19") (pin "2") (pinfunction "2_2") (pintype "bidirectional"))
    )
    (net (code "62") (name "Net-(LED_A0-K)") (class "Default")
      (node (ref "LED_A0") (pin "2") (pinfunction "K_2") (pintype "bidirectional"))
      (node (ref "R28") (pin "2") (pinfunction "2_2") (pintype "bidirectional"))
    )
    (net (code "63") (name "Net-(LED_A1-K)") (class "Default")
      (node (ref "LED_A1") (pin "2") (pinfunction "K_2") (pintype "bidirectional"))
      (node (ref "R29") (pin "2") (pinfunction "2_2") (pintype "bidirectional"))
    )
    (net (code "64") (name "Net-(LED_A2-K)") (class "Default")
      (node (ref "LED_A2") (pin "2") (pinfunction "K_2") (pintype "bidirectional"))
      (node (ref "R30") (pin "2") (pinfunction "2_2") (pintype "bidirectional"))
    )
    (net (code "65") (name "Net-(LED_CS-A)") (class "Default")
      (node (ref "LED_CS") (pin "2") (pinfunction "A_2") (pintype "bidirectional"))
      (node (ref "R16") (pin "2") (pinfunction "2_2") (pintype "bidirectional"))
    )
    (net (code "66") (name "Net-(LED_MISO-A)") (class "Default")
      (node (ref "LED_MISO") (pin "2") (pinfunction "A_2") (pintype "bidirectional"))
      (node (ref "R8") (pin "2") (pinfunction "2_2") (pintype "bidirectional"))
    )
    (net (code "67") (name "Net-(LED_Q0-K)") (class "Default")
      (node (ref "LED_Q0") (pin "1") (pinfunction "K_1") (pintype "bidirectional"))
      (node (ref "R20") (pin "2") (pinfunction "2_2") (pintype "bidirectional"))
    )
    (net (code "68") (name "Net-(LED_Q1-K)") (class "Default")
      (node (ref "LED_Q1") (pin "1") (pinfunction "K_1") (pintype "bidirectional"))
      (node (ref "R21") (pin "2") (pinfunction "2_2") (pintype "bidirectional"))
    )
    (net (code "69") (name "Net-(LED_Q2-K)") (class "Default")
      (node (ref "LED_Q2") (pin "1") (pinfunction "K_1") (pintype "bidirectional"))
      (node (ref "R22") (pin "2") (pinfunction "2_2") (pintype "bidirectional"))
    )
    (net (code "70") (name "Net-(LED_Q3-K)") (class "Default")
      (node (ref "LED_Q3") (pin "1") (pinfunction "K_1") (pintype "bidirectional"))
      (node (ref "R23") (pin "2") (pinfunction "2_2") (pintype "bidirectional"))
    )
    (net (code "71") (name "Net-(LED_Q4-K)") (class "Default")
      (node (ref "LED_Q4") (pin "1") (pinfunction "K_1") (pintype "bidirectional"))
      (node (ref "R24") (pin "2") (pinfunction "2_2") (pintype "bidirectional"))
    )
    (net (code "72") (name "Net-(LED_Q5-K)") (class "Default")
      (node (ref "LED_Q5") (pin "1") (pinfunction "K_1") (pintype "bidirectional"))
      (node (ref "R25") (pin "2") (pinfunction "2_2") (pintype "bidirectional"))
    )
    (net (code "73") (name "Net-(LED_Q6-K)") (class "Default")
      (node (ref "LED_Q6") (pin "1") (pinfunction "K_1") (pintype "bidirectional"))
      (node (ref "R26") (pin "2") (pinfunction "2_2") (pintype "bidirectional"))
    )
    (net (code "74") (name "Net-(LED_Q7-K)") (class "Default")
      (node (ref "LED_Q7") (pin "1") (pinfunction "K_1") (pintype "bidirectional"))
      (node (ref "R27") (pin "2") (pinfunction "2_2") (pintype "bidirectional"))
    )
    (net (code "75") (name "Net-(LED_SCK-A)") (class "Default")
      (node (ref "LED_SCK") (pin "2") (pinfunction "A_2") (pintype "bidirectional"))
      (node (ref "R13") (pin "2") (pinfunction "2_2") (pintype "bidirectional"))
    )
    (net (code "76") (name "Net-(SPI-IBIAS)") (class "Default")
      (node (ref "R14") (pin "1") (pinfunction "1_1") (pintype "bidirectional"))
      (node (ref "SPI") (pin "15") (pinfunction "IBIAS_15") (pintype "bidirectional"))
    )
    (net (code "77") (name "Net-(SPI-MOSI)") (class "Default")
      (node (ref "R5") (pin "2") (pinfunction "2_2") (pintype "bidirectional"))
      (node (ref "SPI") (pin "1") (pinfunction "MOSI_1") (pintype "bidirectional"))
    )
    (net (code "78") (name "Net-(TRANSFORMER-PRIMARY_2)") (class "Default")
      (node (ref "C9") (pin "2") (pinfunction "2_2") (pintype "bidirectional"))
      (node (ref "TRANSFORMER") (pin "2") (pinfunction "PRIMARY_2_2") (pintype "bidirectional"))
    )
    (net (code "79") (name "Net-(TRANSFORMER-SECONDARY_2)") (class "Default")
      (node (ref "C10") (pin "1") (pinfunction "1_1") (pintype "bidirectional"))
      (node (ref "TRANSFORMER") (pin "5") (pinfunction "SECONDARY_2_5") (pintype "bidirectional"))
    )
    (net (code "80") (name "unconnected-(COLD_JUNCTION-NC-Pad8)") (class "Default")
      (node (ref "COLD_JUNCTION") (pin "8") (pinfunction "NC_8") (pintype "no_connect"))
    )
    (net (code "81") (name "unconnected-(D-TYPE-NC-Pad21)") (class "Default")
      (node (ref "D-TYPE") (pin "21") (pinfunction "NC_21") (pintype "no_connect"))
    )
    (net (code "82") (name "unconnected-(PS_-3.3V-NC-Pad4)") (class "Default")
      (node (ref "PS_-3.3V") (pin "4") (pinfunction "NC_4") (pintype "no_connect"))
    )
    (net (code "83") (name "unconnected-(PS_12V-CASE_1-PadC1)") (class "Default")
      (node (ref "PS_12V") (pin "C1") (pinfunction "CASE_1_C1") (pintype "bidirectional"))
    )
    (net (code "84") (name "unconnected-(PS_12V-CASE_2-PadC2)") (class "Default")
      (node (ref "PS_12V") (pin "C2") (pinfunction "CASE_2_C2") (pintype "bidirectional"))
    )
    (net (code "85") (name "unconnected-(U$1-P$1-PadTHROUGH_HOLE)") (class "Default")
      (node (ref "U$1") (pin "THROUGH_HOLE") (pinfunction "P$1_THROUGH_HOLE") (pintype "no_connect"))
    )
    (net (code "86") (name "unconnected-(U$2-P$1-PadTHROUGH_HOLE)") (class "Default")
      (node (ref "U$2") (pin "THROUGH_HOLE") (pinfunction "P$1_THROUGH_HOLE") (pintype "no_connect"))
    )
    (net (code "87") (name "unconnected-(U$3-P$1-PadTHROUGH_HOLE)") (class "Default")
      (node (ref "U$3") (pin "THROUGH_HOLE") (pinfunction "P$1_THROUGH_HOLE") (pintype "no_connect"))
    )
    (net (code "88") (name "unconnected-(U$4-P$1-PadTHROUGH_HOLE)") (class "Default")
      (node (ref "U$4") (pin "THROUGH_HOLE") (pinfunction "P$1_THROUGH_HOLE") (pintype "no_connect"))
    )
  )
)
